# headstage.net
KiCad netlist of a schematic drawn in EAGLE
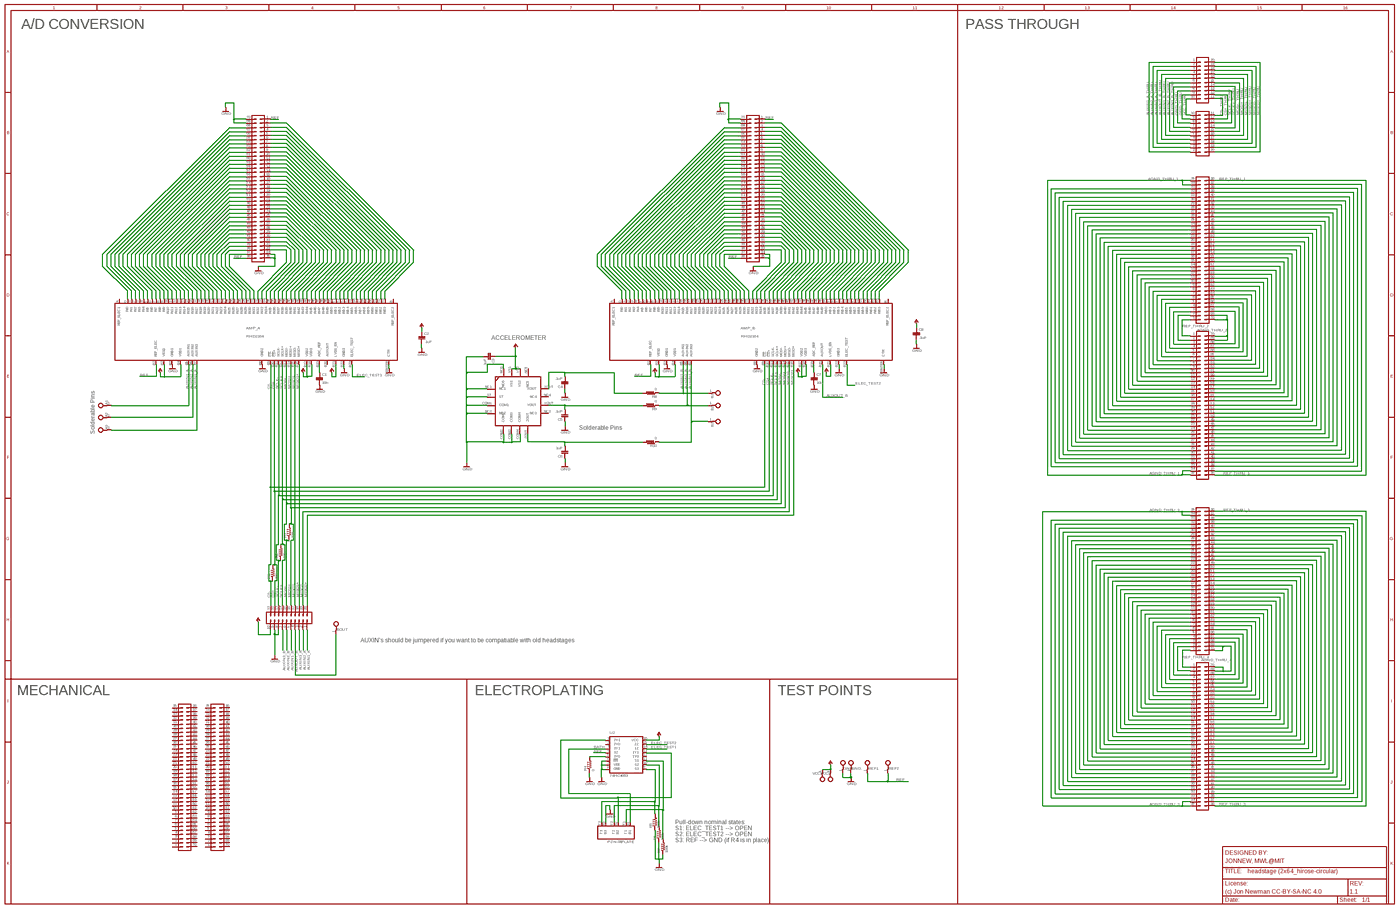
[diagram p0: schematic, sheet 1, overview]
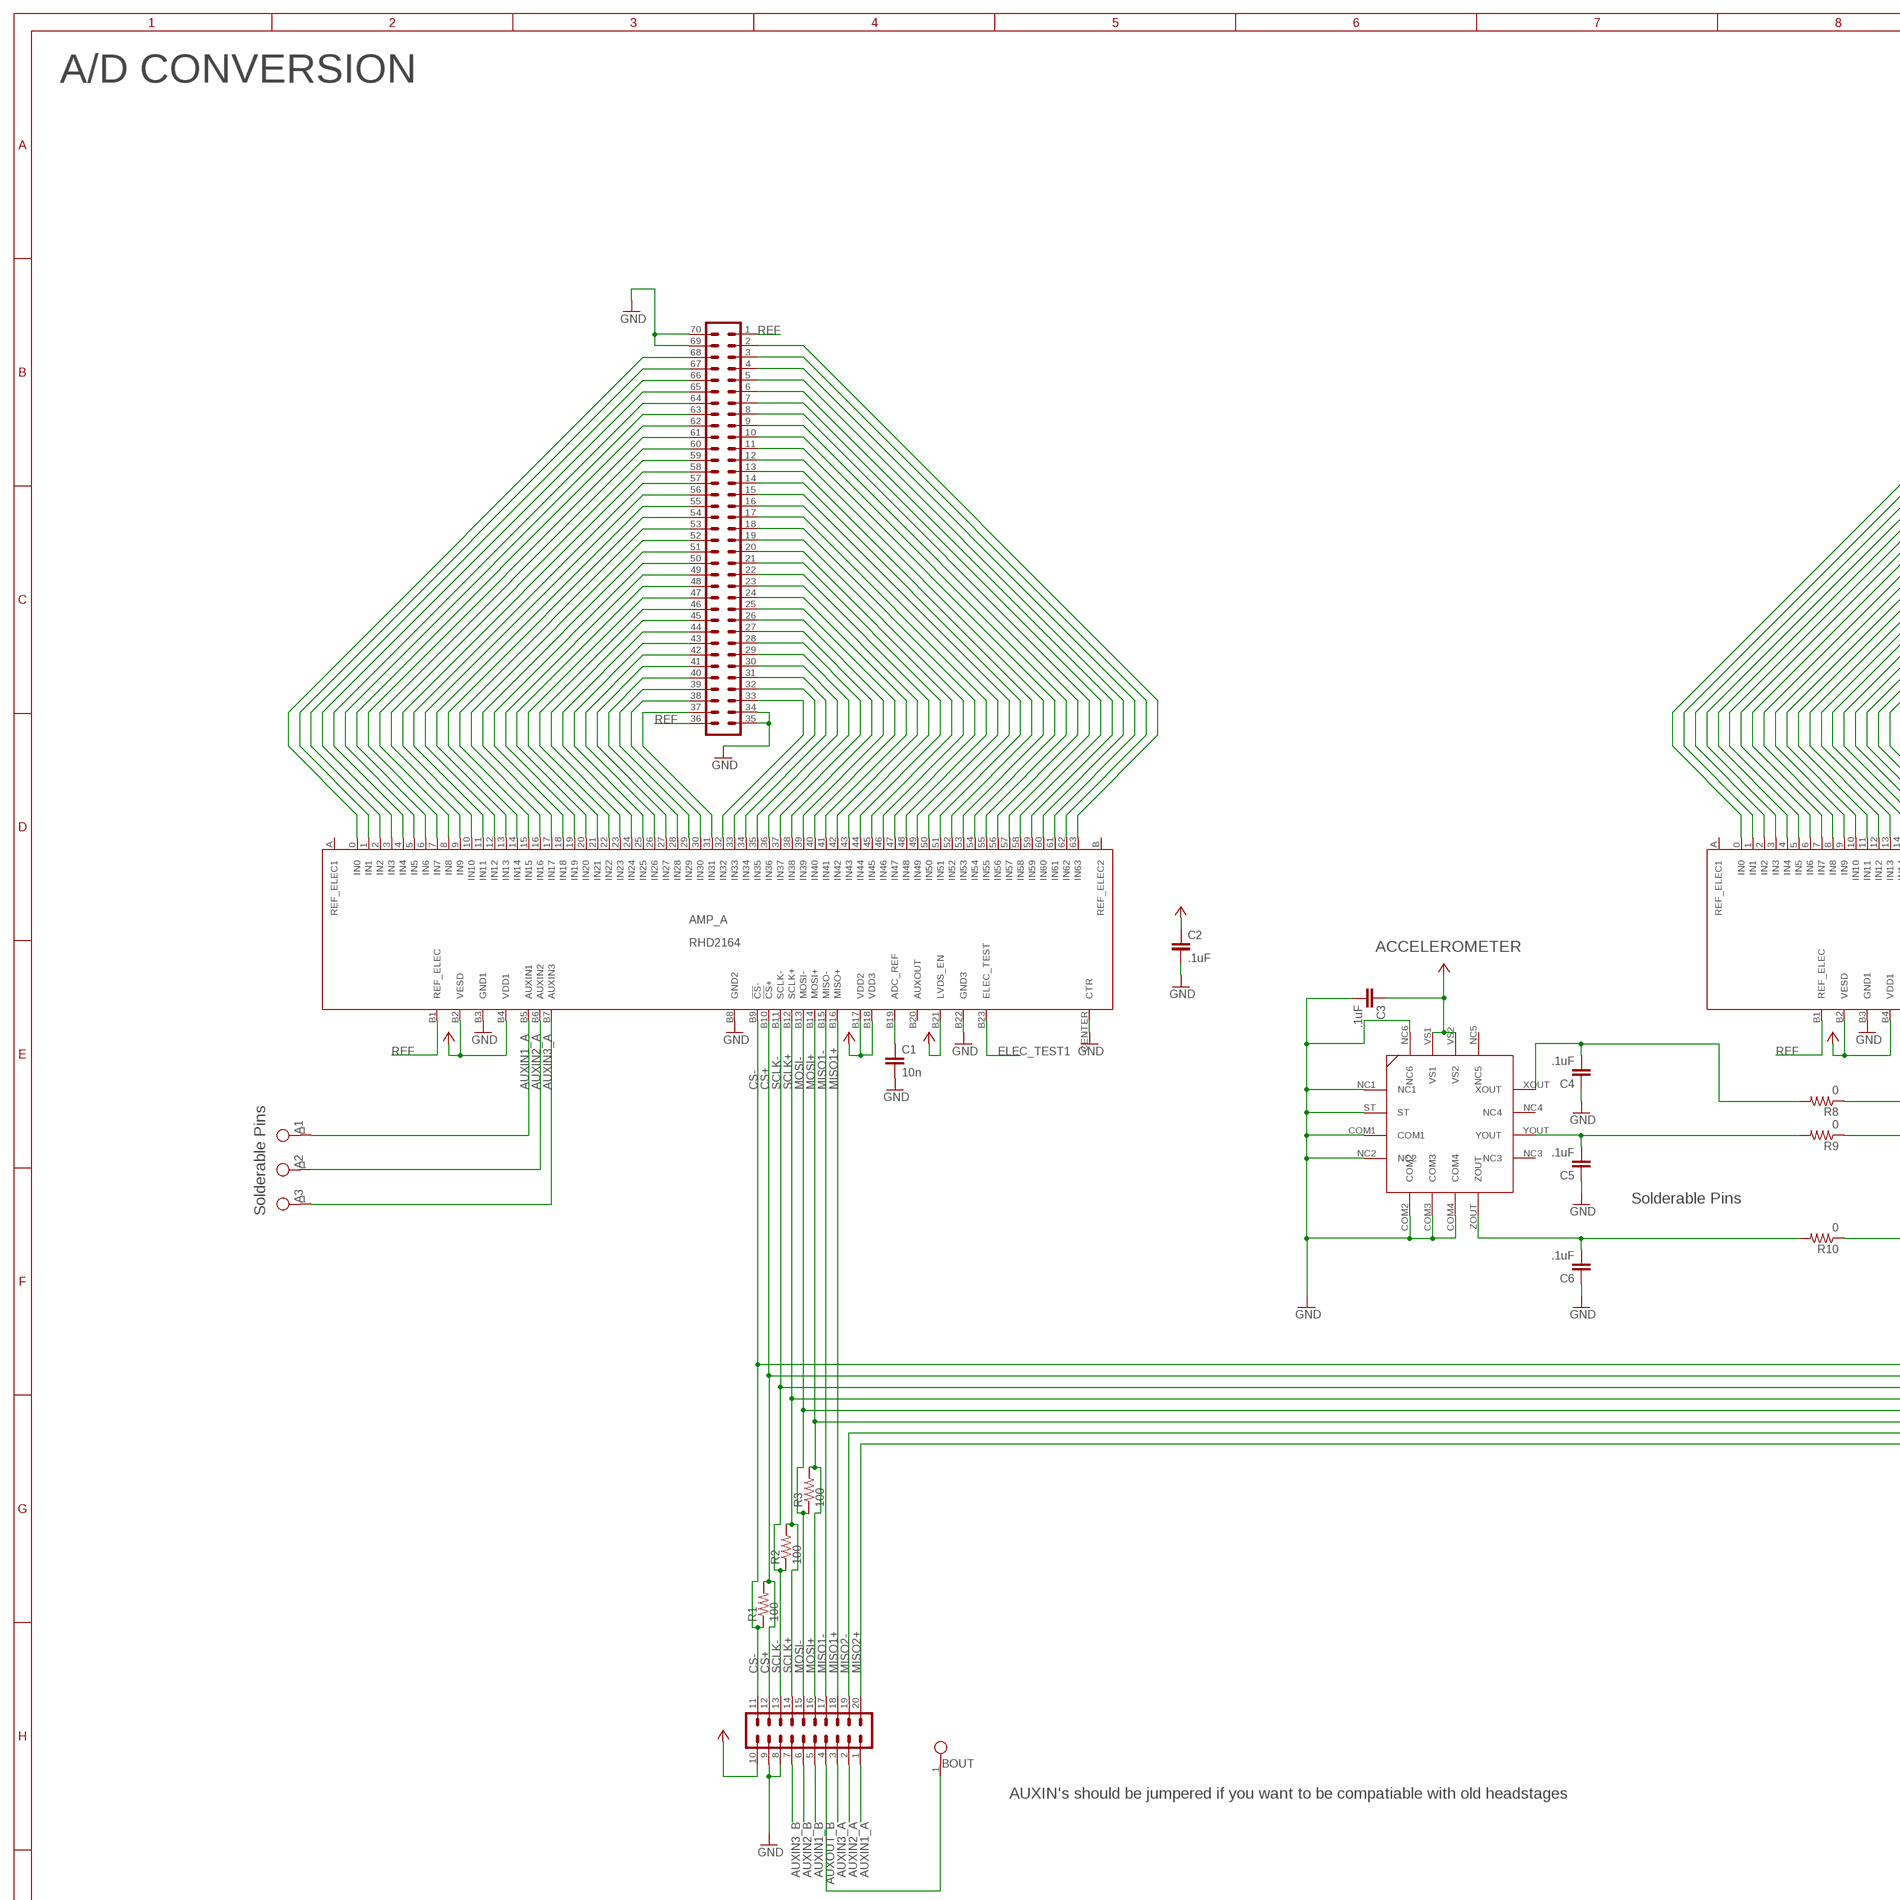
[diagram p1: schematic, sheet 1, part 1 of 4]
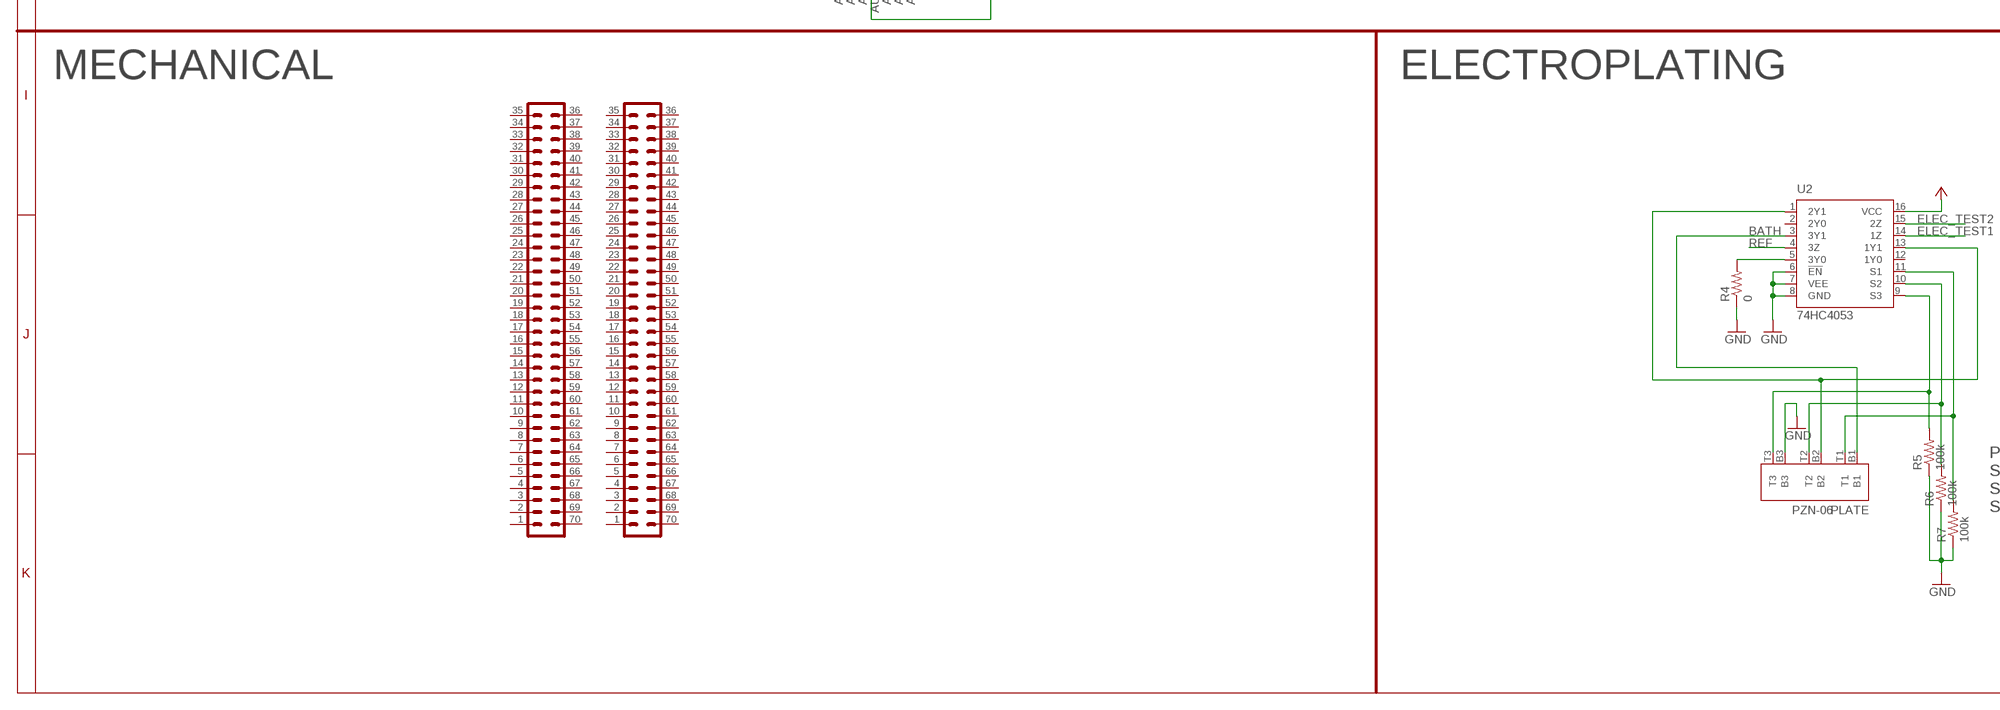
[diagram p2: schematic, sheet 1, part 2 of 4]
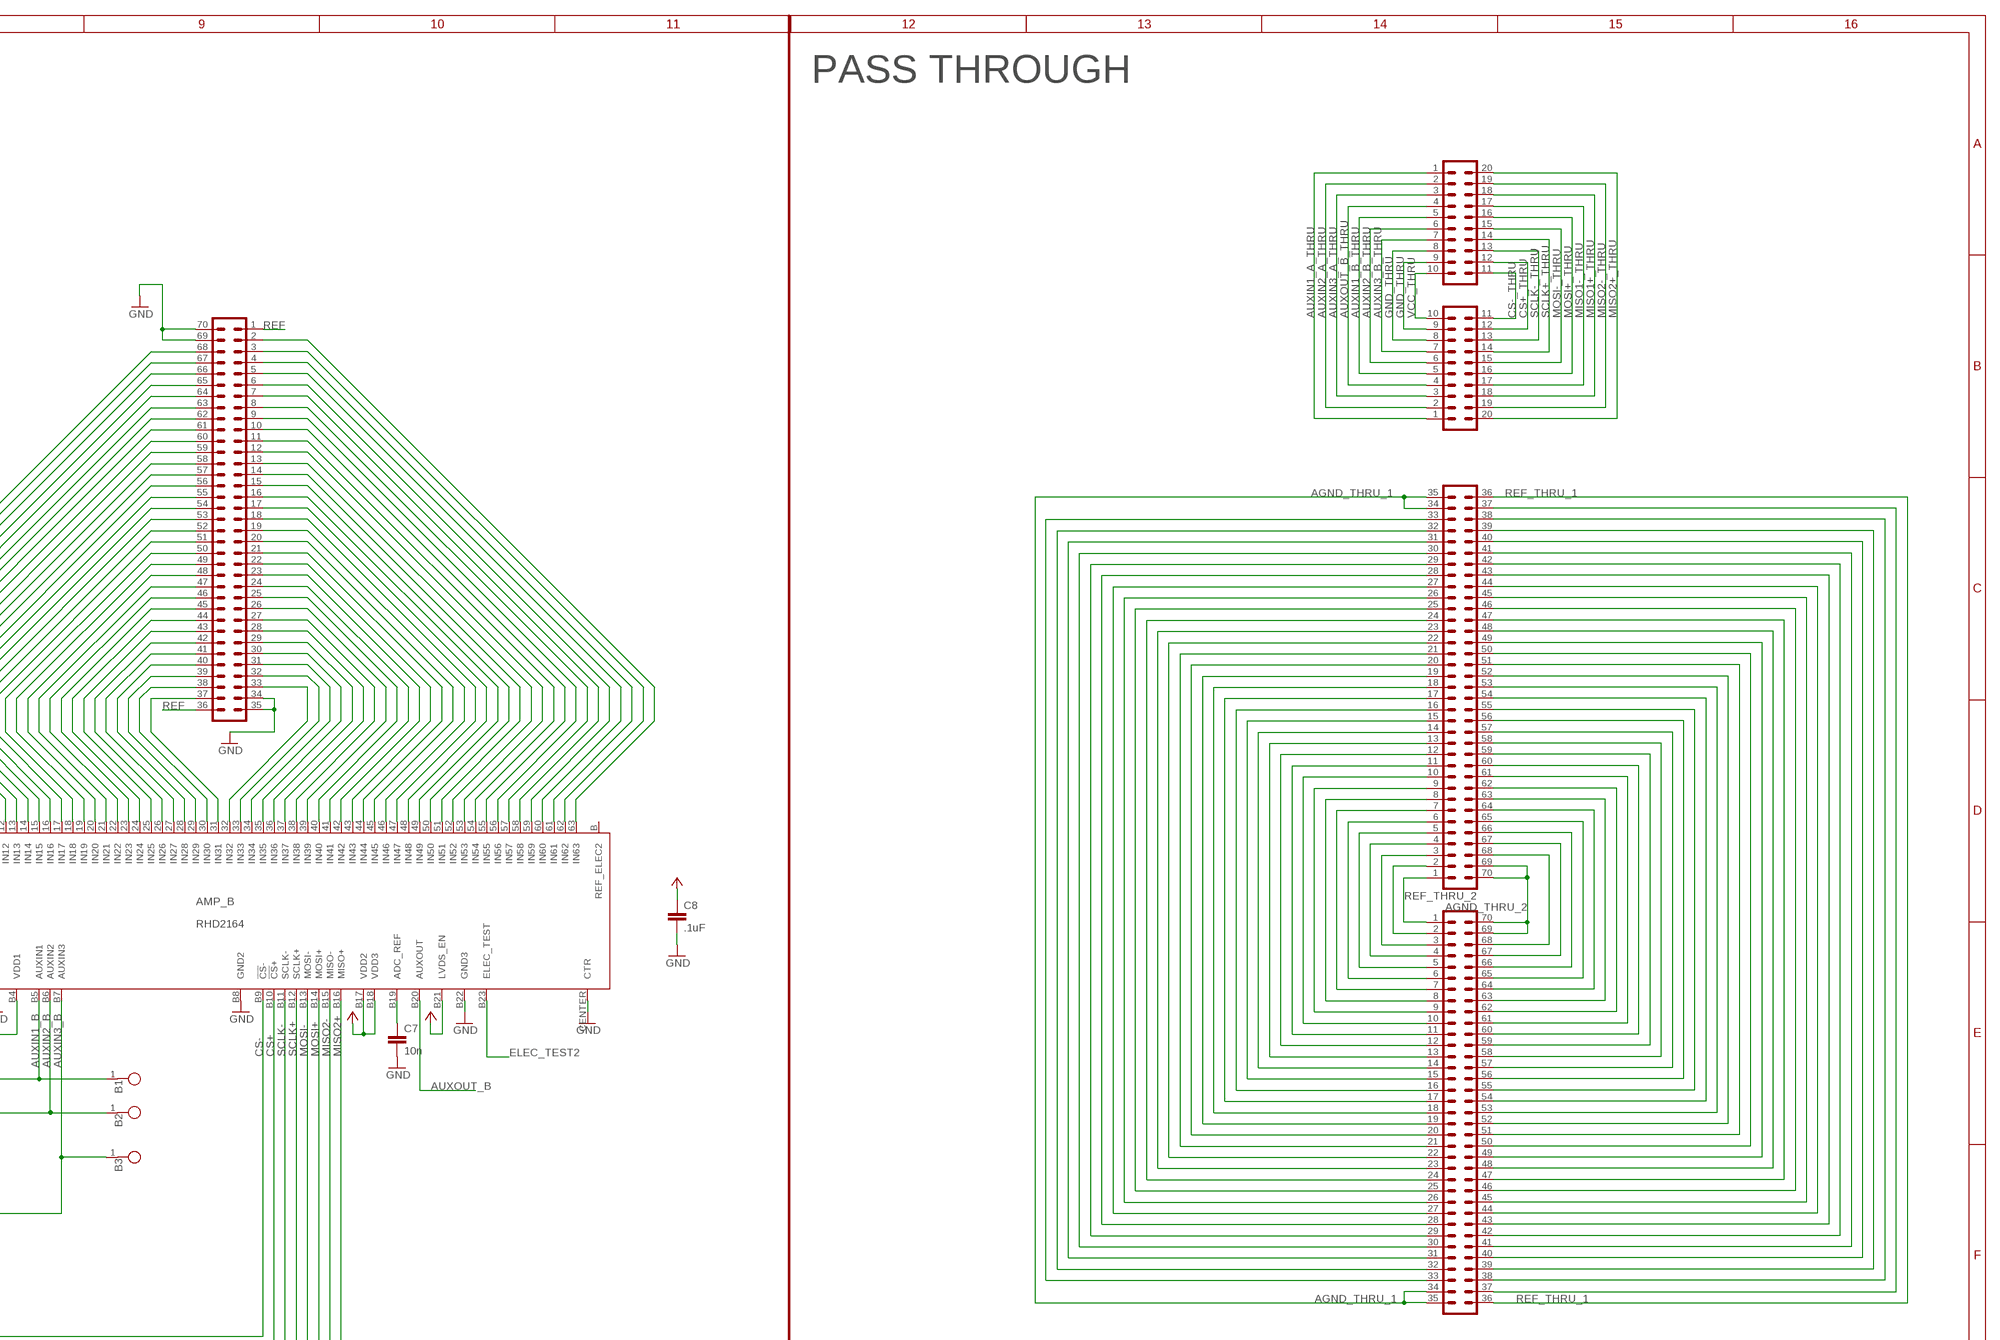
[diagram p3: schematic, sheet 1, part 3 of 4]
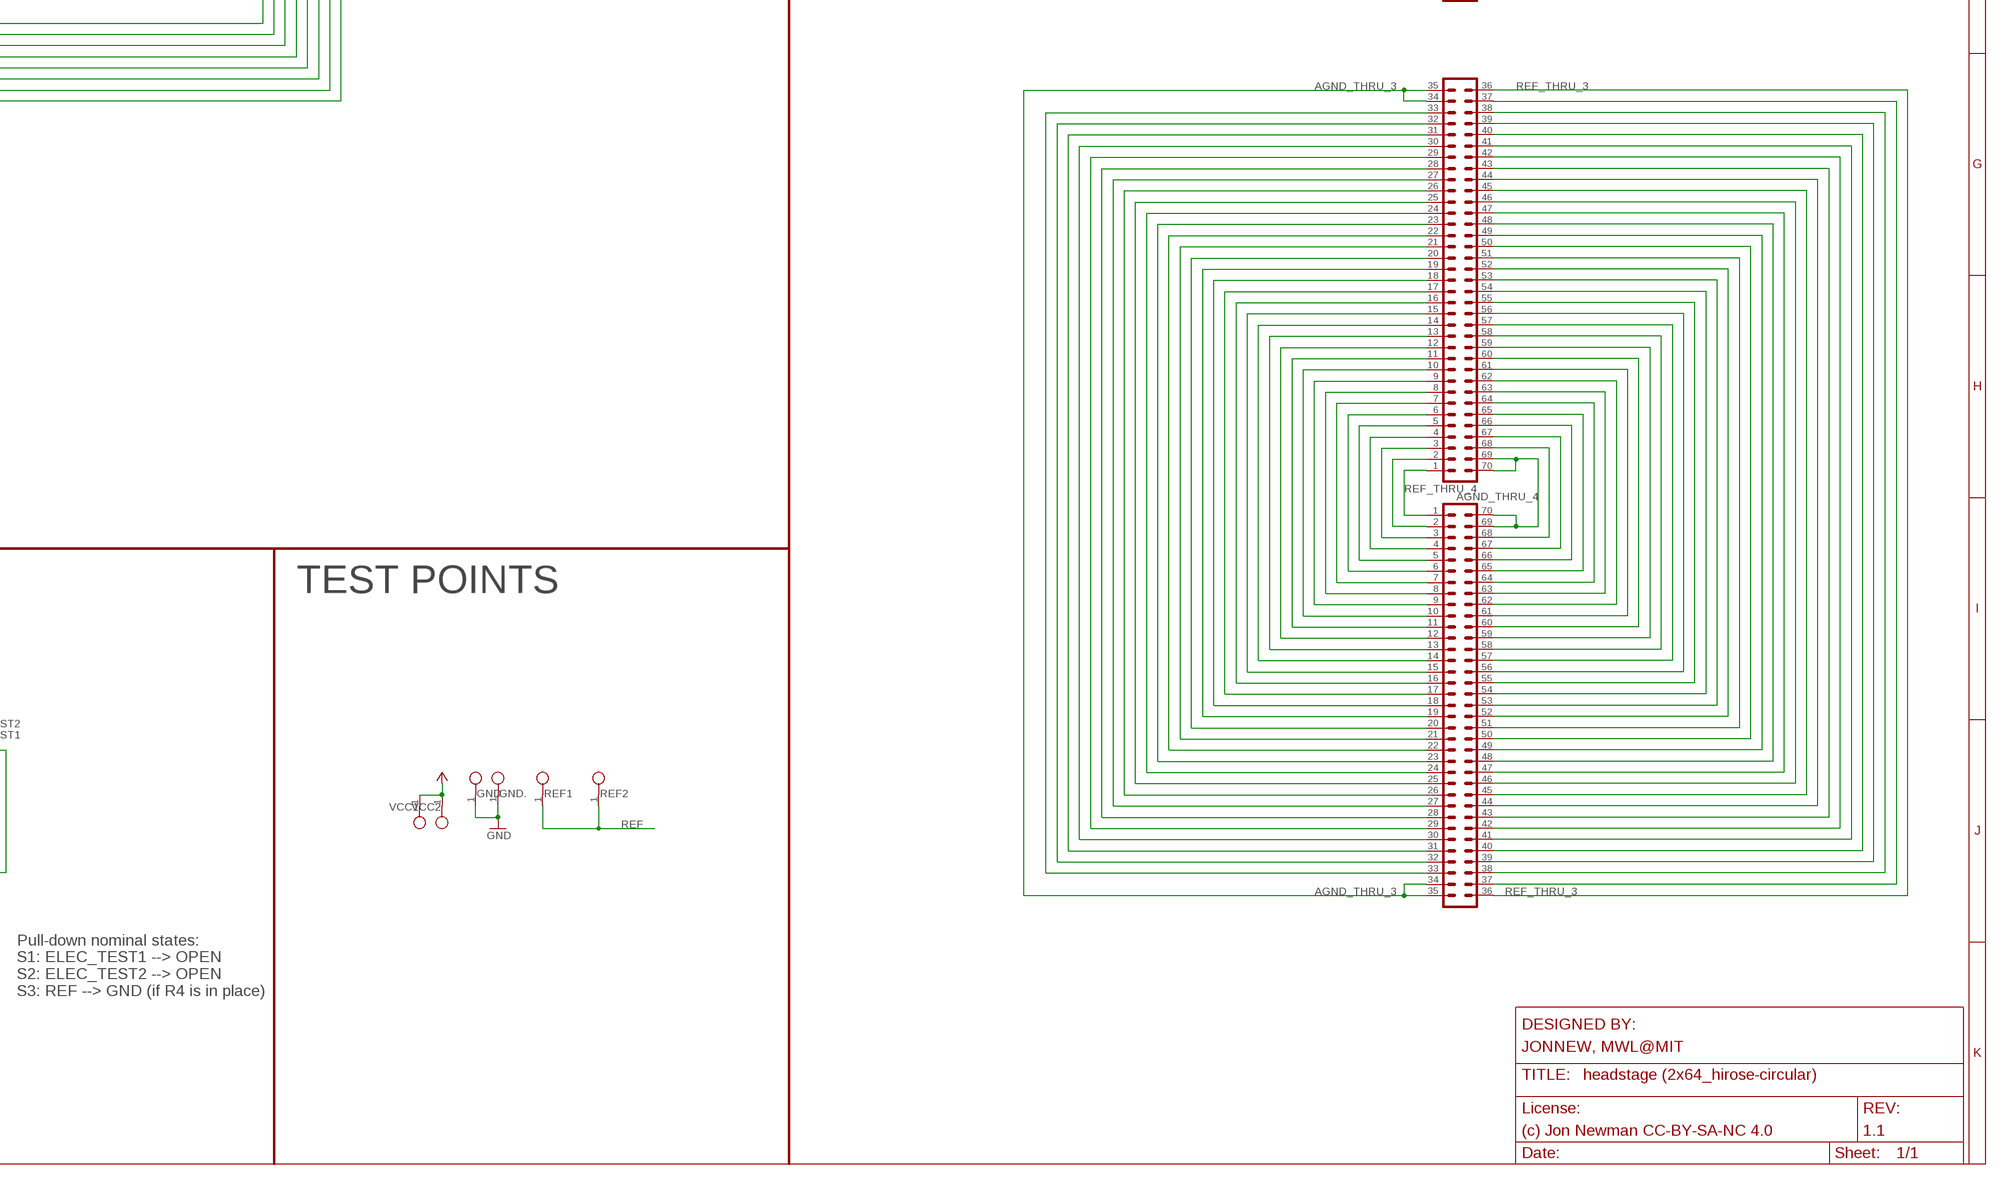
[diagram p4: schematic, sheet 1, part 4 of 4]

(export (version "E")
  (design (tool "Eeschema 10.0.6"))
  (components
    (comp (ref "A1")
      (value "TESTPOINT_SMALL")
      (footprint "eagle-import:TESTPOINT_SMALL")
      (libsource (lib "eagle-import") (part "TESTPOINT_SMALL"))
    )
    (comp (ref "A2")
      (value "TESTPOINT_SMALL")
      (footprint "eagle-import:TESTPOINT_SMALL")
      (libsource (lib "eagle-import") (part "TESTPOINT_SMALL"))
    )
    (comp (ref "A3")
      (value "TESTPOINT_SMALL")
      (footprint "eagle-import:TESTPOINT_SMALL")
      (libsource (lib "eagle-import") (part "TESTPOINT_SMALL"))
    )
    (comp (ref "AIN_BNB")
      (value "DF40REC")
      (footprint "eagle-import:DF40-70REC")
      (libsource (lib "eagle-import") (part "PINHD-2X35_DF40REC"))
    )
    (comp (ref "AIN_BSB")
      (value "DF40REC")
      (footprint "eagle-import:DF40-70REC")
      (libsource (lib "eagle-import") (part "PINHD-2X35_DF40REC"))
    )
    (comp (ref "AMP_A")
      (value "RHD2164")
      (footprint "eagle-import:RHD2164_COB")
      (libsource (lib "eagle-import") (part "RHD2164_COB"))
    )
    (comp (ref "AMP_B")
      (value "RHD2164")
      (footprint "eagle-import:RHD2164_COB")
      (libsource (lib "eagle-import") (part "RHD2164_COB"))
    )
    (comp (ref "ATHRU_BEB")
      (value "DF40REC")
      (footprint "eagle-import:DF40-70REC")
      (libsource (lib "eagle-import") (part "PINHD-2X35_DF40REC"))
    )
    (comp (ref "ATHRU_BWB")
      (value "DF40REC")
      (footprint "eagle-import:DF40-70REC")
      (libsource (lib "eagle-import") (part "PINHD-2X35_DF40REC"))
    )
    (comp (ref "ATHRU_TEB")
      (value "DF40HEAD")
      (footprint "eagle-import:DF40-70HEAD")
      (libsource (lib "eagle-import") (part "PINHD-2X35_DF40HEAD"))
    )
    (comp (ref "ATHRU_TWB")
      (value "DF40HEAD")
      (footprint "eagle-import:DF40-70HEAD")
      (libsource (lib "eagle-import") (part "PINHD-2X35_DF40HEAD"))
    )
    (comp (ref "B1")
      (value "TESTPOINT_SMALL")
      (footprint "eagle-import:TESTPOINT_SMALL")
      (libsource (lib "eagle-import") (part "TESTPOINT_SMALL"))
    )
    (comp (ref "B2")
      (value "TESTPOINT_SMALL")
      (footprint "eagle-import:TESTPOINT_SMALL")
      (libsource (lib "eagle-import") (part "TESTPOINT_SMALL"))
    )
    (comp (ref "B3")
      (value "TESTPOINT_SMALL")
      (footprint "eagle-import:TESTPOINT_SMALL")
      (libsource (lib "eagle-import") (part "TESTPOINT_SMALL"))
    )
    (comp (ref "BOUT")
      (value "TESTPOINT_SMALL")
      (footprint "eagle-import:TESTPOINT_SMALL")
      (libsource (lib "eagle-import") (part "TESTPOINT_SMALL"))
    )
    (comp (ref "C1")
      (value "10n")
      (footprint "eagle-import:0201")
      (libsource (lib "eagle-import") (part "C_0201"))
    )
    (comp (ref "C2")
      (value ".1uF")
      (footprint "eagle-import:0402")
      (libsource (lib "eagle-import") (part "C_0402"))
    )
    (comp (ref "C3")
      (value ".1uF")
      (footprint "eagle-import:0402")
      (libsource (lib "eagle-import") (part "headstage_C_0402"))
    )
    (comp (ref "C4")
      (value ".1uF")
      (footprint "eagle-import:0402")
      (libsource (lib "eagle-import") (part "jonnew_C_0402"))
    )
    (comp (ref "C5")
      (value ".1uF")
      (footprint "eagle-import:0402")
      (libsource (lib "eagle-import") (part "jonnew_C_0402"))
    )
    (comp (ref "C6")
      (value ".1uF")
      (footprint "eagle-import:0402")
      (libsource (lib "eagle-import") (part "jonnew_C_0402"))
    )
    (comp (ref "C7")
      (value "10n")
      (footprint "eagle-import:0201")
      (libsource (lib "eagle-import") (part "C_0201"))
    )
    (comp (ref "C8")
      (value ".1uF")
      (footprint "eagle-import:0402")
      (libsource (lib "eagle-import") (part "C_0402"))
    )
    (comp (ref "DIO_TEA")
      (value "DF40HEAD")
      (footprint "eagle-import:DF40-20HEAD")
      (libsource (lib "eagle-import") (part "PINHD-2X10_DF40-20HEAD"))
    )
    (comp (ref "DTHRU_BNA")
      (value "DF40REC")
      (footprint "eagle-import:DF40-20REC")
      (libsource (lib "eagle-import") (part "PINHD-2X10_DF40-20REC"))
    )
    (comp (ref "DTHRU_TNA")
      (value "DF40HEAD")
      (footprint "eagle-import:DF40-20HEAD")
      (libsource (lib "eagle-import") (part "PINHD-2X10_DF40-20HEAD"))
    )
    (comp (ref "GND")
      (value "GND")
      (footprint "eagle-import:TESTPOINT_SMALL")
      (libsource (lib "eagle-import") (part "TESTPOINT_SMALL"))
    )
    (comp (ref "GND.")
      (value "GND")
      (footprint "eagle-import:TESTPOINT_SMALL")
      (libsource (lib "eagle-import") (part "TESTPOINT_SMALL"))
    )
    (comp (ref "MECH_TNB")
      (value "DF40HEAD")
      (footprint "eagle-import:DF40-70HEAD")
      (libsource (lib "eagle-import") (part "PINHD-2X35_DF40HEAD"))
    )
    (comp (ref "MECH_TSB")
      (value "DF40HEAD")
      (footprint "eagle-import:DF40-70HEAD")
      (libsource (lib "eagle-import") (part "PINHD-2X35_DF40HEAD"))
    )
    (comp (ref "PLATE")
      (value "PZN-06")
      (footprint "eagle-import:OMNETICS_PZN-06-AA")
      (libsource (lib "eagle-import") (part "OMNETICS_PZN-06_SMD"))
    )
    (comp (ref "R1")
      (value "100")
      (footprint "eagle-import:0201")
      (libsource (lib "eagle-import") (part "jonnew_R_0201"))
    )
    (comp (ref "R2")
      (value "100")
      (footprint "eagle-import:0201")
      (libsource (lib "eagle-import") (part "jonnew_R_0201"))
    )
    (comp (ref "R3")
      (value "100")
      (footprint "eagle-import:0201")
      (libsource (lib "eagle-import") (part "jonnew_R_0201"))
    )
    (comp (ref "R4")
      (value "0")
      (footprint "eagle-import:0402")
      (libsource (lib "eagle-import") (part "R_0402"))
    )
    (comp (ref "R5")
      (value "100k")
      (footprint "eagle-import:0201")
      (libsource (lib "eagle-import") (part "R_0201"))
    )
    (comp (ref "R6")
      (value "100k")
      (footprint "eagle-import:0201")
      (libsource (lib "eagle-import") (part "R_0201"))
    )
    (comp (ref "R7")
      (value "100k")
      (footprint "eagle-import:0201")
      (libsource (lib "eagle-import") (part "R_0201"))
    )
    (comp (ref "R8")
      (value "0")
      (footprint "eagle-import:0201")
      (libsource (lib "eagle-import") (part "jonnew_R_0201"))
    )
    (comp (ref "R9")
      (value "0")
      (footprint "eagle-import:0201")
      (libsource (lib "eagle-import") (part "jonnew_R_0201"))
    )
    (comp (ref "R10")
      (value "0")
      (footprint "eagle-import:0201")
      (libsource (lib "eagle-import") (part "jonnew_R_0201"))
    )
    (comp (ref "REF1")
      (value "REF")
      (footprint "eagle-import:TESTPOINT_SMALL")
      (libsource (lib "eagle-import") (part "TESTPOINT_SMALL"))
    )
    (comp (ref "REF2")
      (value "REF")
      (footprint "eagle-import:TESTPOINT_SMALL")
      (libsource (lib "eagle-import") (part "TESTPOINT_SMALL"))
    )
    (comp (ref "U1")
      (value "ADXL335")
      (footprint "eagle-import:ADXL335")
      (libsource (lib "eagle-import") (part "ADXL335"))
    )
    (comp (ref "U2")
      (value "74HC4053")
      (footprint "eagle-import:TSSOP-16")
      (libsource (lib "eagle-import") (part "74HC4053_TSSOP-16"))
    )
    (comp (ref "VCC1")
      (value "VCC")
      (footprint "eagle-import:TESTPOINT_SMALL")
      (libsource (lib "eagle-import") (part "TESTPOINT_SMALL"))
    )
    (comp (ref "VCC2")
      (value "VCC")
      (footprint "eagle-import:TESTPOINT_SMALL")
      (libsource (lib "eagle-import") (part "TESTPOINT_SMALL"))
    )
  )
  (nets
    (net (code "1") (name "/AGND_THRU_1") (class "Default")
      (node (ref "ATHRU_BWB") (pin "34") (pinfunction "34_34") (pintype "bidirectional"))
      (node (ref "ATHRU_BWB") (pin "35") (pinfunction "35_35") (pintype "bidirectional"))
      (node (ref "ATHRU_TWB") (pin "34") (pinfunction "34_34") (pintype "bidirectional"))
      (node (ref "ATHRU_TWB") (pin "35") (pinfunction "35_35") (pintype "bidirectional"))
    )
    (net (code "2") (name "/AGND_THRU_2") (class "Default")
      (node (ref "ATHRU_BWB") (pin "69") (pinfunction "69_69") (pintype "bidirectional"))
      (node (ref "ATHRU_BWB") (pin "70") (pinfunction "70_70") (pintype "bidirectional"))
      (node (ref "ATHRU_TWB") (pin "69") (pinfunction "69_69") (pintype "bidirectional"))
      (node (ref "ATHRU_TWB") (pin "70") (pinfunction "70_70") (pintype "bidirectional"))
    )
    (net (code "3") (name "/AGND_THRU_3") (class "Default")
      (node (ref "ATHRU_BEB") (pin "34") (pinfunction "34_34") (pintype "bidirectional"))
      (node (ref "ATHRU_BEB") (pin "35") (pinfunction "35_35") (pintype "bidirectional"))
      (node (ref "ATHRU_TEB") (pin "34") (pinfunction "34_34") (pintype "bidirectional"))
      (node (ref "ATHRU_TEB") (pin "35") (pinfunction "35_35") (pintype "bidirectional"))
    )
    (net (code "4") (name "/AGND_THRU_4") (class "Default")
      (node (ref "ATHRU_BEB") (pin "69") (pinfunction "69_69") (pintype "bidirectional"))
      (node (ref "ATHRU_BEB") (pin "70") (pinfunction "70_70") (pintype "bidirectional"))
      (node (ref "ATHRU_TEB") (pin "69") (pinfunction "69_69") (pintype "bidirectional"))
      (node (ref "ATHRU_TEB") (pin "70") (pinfunction "70_70") (pintype "bidirectional"))
    )
    (net (code "5") (name "/AUXIN1_A") (class "Default")
      (node (ref "A1") (pin "1") (pinfunction "1_1") (pintype "passive"))
      (node (ref "AMP_A") (pin "B5") (pinfunction "AUXIN1_B5") (pintype "input"))
      (node (ref "DIO_TEA") (pin "1") (pinfunction "1_1") (pintype "bidirectional"))
    )
    (net (code "6") (name "/AUXIN1_A_THRU") (class "Default")
      (node (ref "DTHRU_BNA") (pin "1") (pinfunction "1_1") (pintype "bidirectional"))
      (node (ref "DTHRU_TNA") (pin "1") (pinfunction "1_1") (pintype "bidirectional"))
    )
    (net (code "7") (name "/AUXIN1_B") (class "Default")
      (node (ref "AMP_B") (pin "B5") (pinfunction "AUXIN1_B5") (pintype "input"))
      (node (ref "B1") (pin "1") (pinfunction "1_1") (pintype "passive"))
      (node (ref "DIO_TEA") (pin "5") (pinfunction "5_5") (pintype "bidirectional"))
      (node (ref "R8") (pin "1") (pinfunction "1_1") (pintype "passive"))
    )
    (net (code "8") (name "/AUXIN1_B_THRU") (class "Default")
      (node (ref "DTHRU_BNA") (pin "5") (pinfunction "5_5") (pintype "bidirectional"))
      (node (ref "DTHRU_TNA") (pin "5") (pinfunction "5_5") (pintype "bidirectional"))
    )
    (net (code "9") (name "/AUXIN2_A") (class "Default")
      (node (ref "A2") (pin "1") (pinfunction "1_1") (pintype "passive"))
      (node (ref "AMP_A") (pin "B6") (pinfunction "AUXIN2_B6") (pintype "input"))
      (node (ref "DIO_TEA") (pin "2") (pinfunction "2_2") (pintype "bidirectional"))
    )
    (net (code "10") (name "/AUXIN2_A_THRU") (class "Default")
      (node (ref "DTHRU_BNA") (pin "2") (pinfunction "2_2") (pintype "bidirectional"))
      (node (ref "DTHRU_TNA") (pin "2") (pinfunction "2_2") (pintype "bidirectional"))
    )
    (net (code "11") (name "/AUXIN2_B") (class "Default")
      (node (ref "AMP_B") (pin "B6") (pinfunction "AUXIN2_B6") (pintype "input"))
      (node (ref "B2") (pin "1") (pinfunction "1_1") (pintype "passive"))
      (node (ref "DIO_TEA") (pin "6") (pinfunction "6_6") (pintype "bidirectional"))
      (node (ref "R9") (pin "1") (pinfunction "1_1") (pintype "passive"))
    )
    (net (code "12") (name "/AUXIN2_B_THRU") (class "Default")
      (node (ref "DTHRU_BNA") (pin "6") (pinfunction "6_6") (pintype "bidirectional"))
      (node (ref "DTHRU_TNA") (pin "6") (pinfunction "6_6") (pintype "bidirectional"))
    )
    (net (code "13") (name "/AUXIN3_A") (class "Default")
      (node (ref "A3") (pin "1") (pinfunction "1_1") (pintype "passive"))
      (node (ref "AMP_A") (pin "B7") (pinfunction "AUXIN3_B7") (pintype "input"))
      (node (ref "DIO_TEA") (pin "3") (pinfunction "3_3") (pintype "bidirectional"))
    )
    (net (code "14") (name "/AUXIN3_A_THRU") (class "Default")
      (node (ref "DTHRU_BNA") (pin "3") (pinfunction "3_3") (pintype "bidirectional"))
      (node (ref "DTHRU_TNA") (pin "3") (pinfunction "3_3") (pintype "bidirectional"))
    )
    (net (code "15") (name "/AUXIN3_B") (class "Default")
      (node (ref "AMP_B") (pin "B7") (pinfunction "AUXIN3_B7") (pintype "input"))
      (node (ref "B3") (pin "1") (pinfunction "1_1") (pintype "passive"))
      (node (ref "DIO_TEA") (pin "7") (pinfunction "7_7") (pintype "bidirectional"))
      (node (ref "R10") (pin "1") (pinfunction "1_1") (pintype "passive"))
    )
    (net (code "16") (name "/AUXIN3_B_THRU") (class "Default")
      (node (ref "DTHRU_BNA") (pin "7") (pinfunction "7_7") (pintype "bidirectional"))
      (node (ref "DTHRU_TNA") (pin "7") (pinfunction "7_7") (pintype "bidirectional"))
    )
    (net (code "17") (name "/AUXOUT_B") (class "Default")
      (node (ref "AMP_B") (pin "B20") (pinfunction "AUXOUT_B20") (pintype "tri_state"))
      (node (ref "BOUT") (pin "1") (pinfunction "1_1") (pintype "passive"))
      (node (ref "DIO_TEA") (pin "4") (pinfunction "4_4") (pintype "bidirectional"))
    )
    (net (code "18") (name "/AUXOUT_B_THRU") (class "Default")
      (node (ref "DTHRU_BNA") (pin "4") (pinfunction "4_4") (pintype "bidirectional"))
      (node (ref "DTHRU_TNA") (pin "4") (pinfunction "4_4") (pintype "bidirectional"))
    )
    (net (code "19") (name "/BATH") (class "Default")
      (node (ref "PLATE") (pin "B1") (pinfunction "B1_B1") (pintype "bidirectional"))
      (node (ref "U2") (pin "3") (pinfunction "3Y1_3") (pintype "bidirectional"))
    )
    (net (code "20") (name "/CS+") (class "Default")
      (node (ref "AMP_A") (pin "B10") (pinfunction "~{CS}+_B10") (pintype "input"))
      (node (ref "AMP_B") (pin "B10") (pinfunction "~{CS}+_B10") (pintype "input"))
      (node (ref "DIO_TEA") (pin "12") (pinfunction "12_12") (pintype "bidirectional"))
      (node (ref "R1") (pin "2") (pinfunction "2_2") (pintype "passive"))
    )
    (net (code "21") (name "/CS+_THRU") (class "Default")
      (node (ref "DTHRU_BNA") (pin "12") (pinfunction "12_12") (pintype "bidirectional"))
      (node (ref "DTHRU_TNA") (pin "12") (pinfunction "12_12") (pintype "bidirectional"))
    )
    (net (code "22") (name "/CS-") (class "Default")
      (node (ref "AMP_A") (pin "B9") (pinfunction "~{CS}-_B9") (pintype "input"))
      (node (ref "AMP_B") (pin "B9") (pinfunction "~{CS}-_B9") (pintype "input"))
      (node (ref "DIO_TEA") (pin "11") (pinfunction "11_11") (pintype "bidirectional"))
      (node (ref "R1") (pin "1") (pinfunction "1_1") (pintype "passive"))
    )
    (net (code "23") (name "/CS-_THRU") (class "Default")
      (node (ref "DTHRU_BNA") (pin "11") (pinfunction "11_11") (pintype "bidirectional"))
      (node (ref "DTHRU_TNA") (pin "11") (pinfunction "11_11") (pintype "bidirectional"))
    )
    (net (code "24") (name "/ELEC_TEST1") (class "Default")
      (node (ref "AMP_A") (pin "B23") (pinfunction "ELEC_TEST_B23") (pintype "input"))
      (node (ref "U2") (pin "14") (pinfunction "1Z_14") (pintype "bidirectional"))
    )
    (net (code "25") (name "/ELEC_TEST2") (class "Default")
      (node (ref "AMP_B") (pin "B23") (pinfunction "ELEC_TEST_B23") (pintype "input"))
      (node (ref "U2") (pin "15") (pinfunction "2Z_15") (pintype "bidirectional"))
    )
    (net (code "26") (name "/GND_THRU") (class "Default")
      (node (ref "DTHRU_BNA") (pin "8") (pinfunction "8_8") (pintype "bidirectional"))
      (node (ref "DTHRU_BNA") (pin "9") (pinfunction "9_9") (pintype "bidirectional"))
      (node (ref "DTHRU_TNA") (pin "8") (pinfunction "8_8") (pintype "bidirectional"))
      (node (ref "DTHRU_TNA") (pin "9") (pinfunction "9_9") (pintype "bidirectional"))
    )
    (net (code "27") (name "/MISO1+") (class "Default")
      (node (ref "AMP_A") (pin "B16") (pinfunction "MISO+_B16") (pintype "output"))
      (node (ref "DIO_TEA") (pin "18") (pinfunction "18_18") (pintype "bidirectional"))
    )
    (net (code "28") (name "/MISO1+_THRU") (class "Default")
      (node (ref "DTHRU_BNA") (pin "18") (pinfunction "18_18") (pintype "bidirectional"))
      (node (ref "DTHRU_TNA") (pin "18") (pinfunction "18_18") (pintype "bidirectional"))
    )
    (net (code "29") (name "/MISO1-") (class "Default")
      (node (ref "AMP_A") (pin "B15") (pinfunction "MISO-_B15") (pintype "output"))
      (node (ref "DIO_TEA") (pin "17") (pinfunction "17_17") (pintype "bidirectional"))
    )
    (net (code "30") (name "/MISO1-_THRU") (class "Default")
      (node (ref "DTHRU_BNA") (pin "17") (pinfunction "17_17") (pintype "bidirectional"))
      (node (ref "DTHRU_TNA") (pin "17") (pinfunction "17_17") (pintype "bidirectional"))
    )
    (net (code "31") (name "/MISO2+") (class "Default")
      (node (ref "AMP_B") (pin "B16") (pinfunction "MISO+_B16") (pintype "output"))
      (node (ref "DIO_TEA") (pin "20") (pinfunction "20_20") (pintype "bidirectional"))
    )
    (net (code "32") (name "/MISO2+_THRU") (class "Default")
      (node (ref "DTHRU_BNA") (pin "20") (pinfunction "20_20") (pintype "bidirectional"))
      (node (ref "DTHRU_TNA") (pin "20") (pinfunction "20_20") (pintype "bidirectional"))
    )
    (net (code "33") (name "/MISO2-") (class "Default")
      (node (ref "AMP_B") (pin "B15") (pinfunction "MISO-_B15") (pintype "output"))
      (node (ref "DIO_TEA") (pin "19") (pinfunction "19_19") (pintype "bidirectional"))
    )
    (net (code "34") (name "/MISO2-_THRU") (class "Default")
      (node (ref "DTHRU_BNA") (pin "19") (pinfunction "19_19") (pintype "bidirectional"))
      (node (ref "DTHRU_TNA") (pin "19") (pinfunction "19_19") (pintype "bidirectional"))
    )
    (net (code "35") (name "/MOSI+") (class "Default")
      (node (ref "AMP_A") (pin "B14") (pinfunction "MOSI+_B14") (pintype "input"))
      (node (ref "AMP_B") (pin "B14") (pinfunction "MOSI+_B14") (pintype "input"))
      (node (ref "DIO_TEA") (pin "16") (pinfunction "16_16") (pintype "bidirectional"))
      (node (ref "R3") (pin "2") (pinfunction "2_2") (pintype "passive"))
    )
    (net (code "36") (name "/MOSI+_THRU") (class "Default")
      (node (ref "DTHRU_BNA") (pin "16") (pinfunction "16_16") (pintype "bidirectional"))
      (node (ref "DTHRU_TNA") (pin "16") (pinfunction "16_16") (pintype "bidirectional"))
    )
    (net (code "37") (name "/MOSI-") (class "Default")
      (node (ref "AMP_A") (pin "B13") (pinfunction "MOSI-_B13") (pintype "input"))
      (node (ref "AMP_B") (pin "B13") (pinfunction "MOSI-_B13") (pintype "input"))
      (node (ref "DIO_TEA") (pin "15") (pinfunction "15_15") (pintype "bidirectional"))
      (node (ref "R3") (pin "1") (pinfunction "1_1") (pintype "passive"))
    )
    (net (code "38") (name "/MOSI-_THRU") (class "Default")
      (node (ref "DTHRU_BNA") (pin "15") (pinfunction "15_15") (pintype "bidirectional"))
      (node (ref "DTHRU_TNA") (pin "15") (pinfunction "15_15") (pintype "bidirectional"))
    )
    (net (code "39") (name "/REF") (class "Default")
      (node (ref "AIN_BNB") (pin "1") (pinfunction "1_1") (pintype "bidirectional"))
      (node (ref "AIN_BNB") (pin "36") (pinfunction "36_36") (pintype "bidirectional"))
      (node (ref "AIN_BSB") (pin "1") (pinfunction "1_1") (pintype "bidirectional"))
      (node (ref "AIN_BSB") (pin "36") (pinfunction "36_36") (pintype "bidirectional"))
      (node (ref "AMP_A") (pin "B1") (pinfunction "REF_ELEC_B1") (pintype "input"))
      (node (ref "AMP_B") (pin "B1") (pinfunction "REF_ELEC_B1") (pintype "input"))
      (node (ref "REF1") (pin "1") (pinfunction "1_1") (pintype "passive"))
      (node (ref "REF2") (pin "1") (pinfunction "1_1") (pintype "passive"))
      (node (ref "U2") (pin "4") (pinfunction "3Z_4") (pintype "bidirectional"))
    )
    (net (code "40") (name "/REF_THRU_1") (class "Default")
      (node (ref "ATHRU_BWB") (pin "36") (pinfunction "36_36") (pintype "bidirectional"))
      (node (ref "ATHRU_TWB") (pin "36") (pinfunction "36_36") (pintype "bidirectional"))
    )
    (net (code "41") (name "/REF_THRU_2") (class "Default")
      (node (ref "ATHRU_BWB") (pin "1") (pinfunction "1_1") (pintype "bidirectional"))
      (node (ref "ATHRU_TWB") (pin "1") (pinfunction "1_1") (pintype "bidirectional"))
    )
    (net (code "42") (name "/REF_THRU_3") (class "Default")
      (node (ref "ATHRU_BEB") (pin "36") (pinfunction "36_36") (pintype "bidirectional"))
      (node (ref "ATHRU_TEB") (pin "36") (pinfunction "36_36") (pintype "bidirectional"))
    )
    (net (code "43") (name "/REF_THRU_4") (class "Default")
      (node (ref "ATHRU_BEB") (pin "1") (pinfunction "1_1") (pintype "bidirectional"))
      (node (ref "ATHRU_TEB") (pin "1") (pinfunction "1_1") (pintype "bidirectional"))
    )
    (net (code "44") (name "/SCLK+") (class "Default")
      (node (ref "AMP_A") (pin "B12") (pinfunction "SCLK+_B12") (pintype "input"))
      (node (ref "AMP_B") (pin "B12") (pinfunction "SCLK+_B12") (pintype "input"))
      (node (ref "DIO_TEA") (pin "14") (pinfunction "14_14") (pintype "bidirectional"))
      (node (ref "R2") (pin "2") (pinfunction "2_2") (pintype "passive"))
    )
    (net (code "45") (name "/SCLK+_THRU") (class "Default")
      (node (ref "DTHRU_BNA") (pin "14") (pinfunction "14_14") (pintype "bidirectional"))
      (node (ref "DTHRU_TNA") (pin "14") (pinfunction "14_14") (pintype "bidirectional"))
    )
    (net (code "46") (name "/SCLK-") (class "Default")
      (node (ref "AMP_A") (pin "B11") (pinfunction "SCLK-_B11") (pintype "input"))
      (node (ref "AMP_B") (pin "B11") (pinfunction "SCLK-_B11") (pintype "input"))
      (node (ref "DIO_TEA") (pin "13") (pinfunction "13_13") (pintype "bidirectional"))
      (node (ref "R2") (pin "1") (pinfunction "1_1") (pintype "passive"))
    )
    (net (code "47") (name "/SCLK-_THRU") (class "Default")
      (node (ref "DTHRU_BNA") (pin "13") (pinfunction "13_13") (pintype "bidirectional"))
      (node (ref "DTHRU_TNA") (pin "13") (pinfunction "13_13") (pintype "bidirectional"))
    )
    (net (code "48") (name "/VCC_THRU") (class "Default")
      (node (ref "DTHRU_BNA") (pin "10") (pinfunction "10_10") (pintype "bidirectional"))
      (node (ref "DTHRU_TNA") (pin "10") (pinfunction "10_10") (pintype "bidirectional"))
    )
    (net (code "49") (name "GND") (class "Default")
      (node (ref "AIN_BNB") (pin "34") (pinfunction "34_34") (pintype "bidirectional"))
      (node (ref "AIN_BNB") (pin "35") (pinfunction "35_35") (pintype "bidirectional"))
      (node (ref "AIN_BNB") (pin "69") (pinfunction "69_69") (pintype "bidirectional"))
      (node (ref "AIN_BNB") (pin "70") (pinfunction "70_70") (pintype "bidirectional"))
      (node (ref "AIN_BSB") (pin "34") (pinfunction "34_34") (pintype "bidirectional"))
      (node (ref "AIN_BSB") (pin "35") (pinfunction "35_35") (pintype "bidirectional"))
      (node (ref "AIN_BSB") (pin "69") (pinfunction "69_69") (pintype "bidirectional"))
      (node (ref "AIN_BSB") (pin "70") (pinfunction "70_70") (pintype "bidirectional"))
      (node (ref "AMP_A") (pin "B22") (pinfunction "GND3_B22") (pintype "power_in"))
      (node (ref "AMP_A") (pin "B3") (pinfunction "GND1_B3") (pintype "power_in"))
      (node (ref "AMP_A") (pin "B8") (pinfunction "GND2_B8") (pintype "power_in"))
      (node (ref "AMP_A") (pin "CENTER") (pinfunction "CTR_CENTER") (pintype "power_in"))
      (node (ref "AMP_B") (pin "B22") (pinfunction "GND3_B22") (pintype "power_in"))
      (node (ref "AMP_B") (pin "B3") (pinfunction "GND1_B3") (pintype "power_in"))
      (node (ref "AMP_B") (pin "B8") (pinfunction "GND2_B8") (pintype "power_in"))
      (node (ref "AMP_B") (pin "CENTER") (pinfunction "CTR_CENTER") (pintype "power_in"))
      (node (ref "C1") (pin "2") (pinfunction "2_2") (pintype "passive"))
      (node (ref "C2") (pin "2") (pinfunction "2_2") (pintype "passive"))
      (node (ref "C3") (pin "2") (pinfunction "2_2") (pintype "passive"))
      (node (ref "C4") (pin "1") (pinfunction "1_1") (pintype "passive"))
      (node (ref "C5") (pin "1") (pinfunction "1_1") (pintype "passive"))
      (node (ref "C6") (pin "1") (pinfunction "1_1") (pintype "passive"))
      (node (ref "C7") (pin "2") (pinfunction "2_2") (pintype "passive"))
      (node (ref "C8") (pin "2") (pinfunction "2_2") (pintype "passive"))
      (node (ref "DIO_TEA") (pin "8") (pinfunction "8_8") (pintype "bidirectional"))
      (node (ref "DIO_TEA") (pin "9") (pinfunction "9_9") (pintype "bidirectional"))
      (node (ref "GND") (pin "1") (pinfunction "1_1") (pintype "passive"))
      (node (ref "GND.") (pin "1") (pinfunction "1_1") (pintype "passive"))
      (node (ref "PLATE") (pin "B3") (pinfunction "B3_B3") (pintype "bidirectional"))
      (node (ref "R4") (pin "1") (pinfunction "1_1") (pintype "passive"))
      (node (ref "R5") (pin "1") (pinfunction "1_1") (pintype "passive"))
      (node (ref "R6") (pin "1") (pinfunction "1_1") (pintype "passive"))
      (node (ref "R7") (pin "1") (pinfunction "1_1") (pintype "passive"))
      (node (ref "U1") (pin "COM1") (pinfunction "COM1_COM1") (pintype "bidirectional"))
      (node (ref "U1") (pin "COM2") (pinfunction "COM2_COM2") (pintype "bidirectional"))
      (node (ref "U1") (pin "COM3") (pinfunction "COM3_COM3") (pintype "bidirectional"))
      (node (ref "U1") (pin "COM4") (pinfunction "COM4_COM4") (pintype "bidirectional"))
      (node (ref "U1") (pin "NC1") (pinfunction "NC1_NC1") (pintype "bidirectional"))
      (node (ref "U1") (pin "NC2") (pinfunction "NC2_NC2") (pintype "bidirectional"))
      (node (ref "U1") (pin "NC6") (pinfunction "NC6_NC6") (pintype "bidirectional"))
      (node (ref "U1") (pin "ST") (pinfunction "ST_ST") (pintype "bidirectional"))
      (node (ref "U2") (pin "6") (pinfunction "~{EN}_6") (pintype "input"))
      (node (ref "U2") (pin "7") (pinfunction "VEE_7") (pintype "power_in"))
      (node (ref "U2") (pin "8") (pinfunction "GND_8") (pintype "power_in"))
    )
    (net (code "50") (name "Net-(AMP_A-ADC_REF)") (class "Default")
      (node (ref "AMP_A") (pin "B19") (pinfunction "ADC_REF_B19") (pintype "passive"))
      (node (ref "C1") (pin "1") (pinfunction "1_1") (pintype "passive"))
    )
    (net (code "51") (name "Net-(AMP_A-IN0)") (class "Default")
      (node (ref "AIN_BNB") (pin "68") (pinfunction "68_68") (pintype "bidirectional"))
      (node (ref "AMP_A") (pin "0") (pinfunction "IN0_0") (pintype "input"))
    )
    (net (code "52") (name "Net-(AMP_A-IN1)") (class "Default")
      (node (ref "AIN_BNB") (pin "67") (pinfunction "67_67") (pintype "bidirectional"))
      (node (ref "AMP_A") (pin "1") (pinfunction "IN1_1") (pintype "input"))
    )
    (net (code "53") (name "Net-(AMP_A-IN2)") (class "Default")
      (node (ref "AIN_BNB") (pin "66") (pinfunction "66_66") (pintype "bidirectional"))
      (node (ref "AMP_A") (pin "2") (pinfunction "IN2_2") (pintype "input"))
    )
    (net (code "54") (name "Net-(AMP_A-IN3)") (class "Default")
      (node (ref "AIN_BNB") (pin "65") (pinfunction "65_65") (pintype "bidirectional"))
      (node (ref "AMP_A") (pin "3") (pinfunction "IN3_3") (pintype "input"))
    )
    (net (code "55") (name "Net-(AMP_A-IN4)") (class "Default")
      (node (ref "AIN_BNB") (pin "64") (pinfunction "64_64") (pintype "bidirectional"))
      (node (ref "AMP_A") (pin "4") (pinfunction "IN4_4") (pintype "input"))
    )
    (net (code "56") (name "Net-(AMP_A-IN5)") (class "Default")
      (node (ref "AIN_BNB") (pin "63") (pinfunction "63_63") (pintype "bidirectional"))
      (node (ref "AMP_A") (pin "5") (pinfunction "IN5_5") (pintype "input"))
    )
    (net (code "57") (name "Net-(AMP_A-IN6)") (class "Default")
      (node (ref "AIN_BNB") (pin "62") (pinfunction "62_62") (pintype "bidirectional"))
      (node (ref "AMP_A") (pin "6") (pinfunction "IN6_6") (pintype "input"))
    )
    (net (code "58") (name "Net-(AMP_A-IN7)") (class "Default")
      (node (ref "AIN_BNB") (pin "61") (pinfunction "61_61") (pintype "bidirectional"))
      (node (ref "AMP_A") (pin "7") (pinfunction "IN7_7") (pintype "input"))
    )
    (net (code "59") (name "Net-(AMP_A-IN8)") (class "Default")
      (node (ref "AIN_BNB") (pin "60") (pinfunction "60_60") (pintype "bidirectional"))
      (node (ref "AMP_A") (pin "8") (pinfunction "IN8_8") (pintype "input"))
    )
    (net (code "60") (name "Net-(AMP_A-IN9)") (class "Default")
      (node (ref "AIN_BNB") (pin "59") (pinfunction "59_59") (pintype "bidirectional"))
      (node (ref "AMP_A") (pin "9") (pinfunction "IN9_9") (pintype "input"))
    )
    (net (code "61") (name "Net-(AMP_A-IN10)") (class "Default")
      (node (ref "AIN_BNB") (pin "58") (pinfunction "58_58") (pintype "bidirectional"))
      (node (ref "AMP_A") (pin "10") (pinfunction "IN10_10") (pintype "input"))
    )
    (net (code "62") (name "Net-(AMP_A-IN11)") (class "Default")
      (node (ref "AIN_BNB") (pin "57") (pinfunction "57_57") (pintype "bidirectional"))
      (node (ref "AMP_A") (pin "11") (pinfunction "IN11_11") (pintype "input"))
    )
    (net (code "63") (name "Net-(AMP_A-IN12)") (class "Default")
      (node (ref "AIN_BNB") (pin "56") (pinfunction "56_56") (pintype "bidirectional"))
      (node (ref "AMP_A") (pin "12") (pinfunction "IN12_12") (pintype "input"))
    )
    (net (code "64") (name "Net-(AMP_A-IN13)") (class "Default")
      (node (ref "AIN_BNB") (pin "55") (pinfunction "55_55") (pintype "bidirectional"))
      (node (ref "AMP_A") (pin "13") (pinfunction "IN13_13") (pintype "input"))
    )
    (net (code "65") (name "Net-(AMP_A-IN14)") (class "Default")
      (node (ref "AIN_BNB") (pin "54") (pinfunction "54_54") (pintype "bidirectional"))
      (node (ref "AMP_A") (pin "14") (pinfunction "IN14_14") (pintype "input"))
    )
    (net (code "66") (name "Net-(AMP_A-IN15)") (class "Default")
      (node (ref "AIN_BNB") (pin "53") (pinfunction "53_53") (pintype "bidirectional"))
      (node (ref "AMP_A") (pin "15") (pinfunction "IN15_15") (pintype "input"))
    )
    (net (code "67") (name "Net-(AMP_A-IN16)") (class "Default")
      (node (ref "AIN_BNB") (pin "52") (pinfunction "52_52") (pintype "bidirectional"))
      (node (ref "AMP_A") (pin "16") (pinfunction "IN16_16") (pintype "input"))
    )
    (net (code "68") (name "Net-(AMP_A-IN17)") (class "Default")
      (node (ref "AIN_BNB") (pin "51") (pinfunction "51_51") (pintype "bidirectional"))
      (node (ref "AMP_A") (pin "17") (pinfunction "IN17_17") (pintype "input"))
    )
    (net (code "69") (name "Net-(AMP_A-IN18)") (class "Default")
      (node (ref "AIN_BNB") (pin "50") (pinfunction "50_50") (pintype "bidirectional"))
      (node (ref "AMP_A") (pin "18") (pinfunction "IN18_18") (pintype "input"))
    )
    (net (code "70") (name "Net-(AMP_A-IN19)") (class "Default")
      (node (ref "AIN_BNB") (pin "49") (pinfunction "49_49") (pintype "bidirectional"))
      (node (ref "AMP_A") (pin "19") (pinfunction "IN19_19") (pintype "input"))
    )
    (net (code "71") (name "Net-(AMP_A-IN20)") (class "Default")
      (node (ref "AIN_BNB") (pin "48") (pinfunction "48_48") (pintype "bidirectional"))
      (node (ref "AMP_A") (pin "20") (pinfunction "IN20_20") (pintype "input"))
    )
    (net (code "72") (name "Net-(AMP_A-IN21)") (class "Default")
      (node (ref "AIN_BNB") (pin "47") (pinfunction "47_47") (pintype "bidirectional"))
      (node (ref "AMP_A") (pin "21") (pinfunction "IN21_21") (pintype "input"))
    )
    (net (code "73") (name "Net-(AMP_A-IN22)") (class "Default")
      (node (ref "AIN_BNB") (pin "46") (pinfunction "46_46") (pintype "bidirectional"))
      (node (ref "AMP_A") (pin "22") (pinfunction "IN22_22") (pintype "input"))
    )
    (net (code "74") (name "Net-(AMP_A-IN23)") (class "Default")
      (node (ref "AIN_BNB") (pin "45") (pinfunction "45_45") (pintype "bidirectional"))
      (node (ref "AMP_A") (pin "23") (pinfunction "IN23_23") (pintype "input"))
    )
    (net (code "75") (name "Net-(AMP_A-IN24)") (class "Default")
      (node (ref "AIN_BNB") (pin "44") (pinfunction "44_44") (pintype "bidirectional"))
      (node (ref "AMP_A") (pin "24") (pinfunction "IN24_24") (pintype "input"))
    )
    (net (code "76") (name "Net-(AMP_A-IN25)") (class "Default")
      (node (ref "AIN_BNB") (pin "43") (pinfunction "43_43") (pintype "bidirectional"))
      (node (ref "AMP_A") (pin "25") (pinfunction "IN25_25") (pintype "input"))
    )
    (net (code "77") (name "Net-(AMP_A-IN26)") (class "Default")
      (node (ref "AIN_BNB") (pin "42") (pinfunction "42_42") (pintype "bidirectional"))
      (node (ref "AMP_A") (pin "26") (pinfunction "IN26_26") (pintype "input"))
    )
    (net (code "78") (name "Net-(AMP_A-IN27)") (class "Default")
      (node (ref "AIN_BNB") (pin "41") (pinfunction "41_41") (pintype "bidirectional"))
      (node (ref "AMP_A") (pin "27") (pinfunction "IN27_27") (pintype "input"))
    )
    (net (code "79") (name "Net-(AMP_A-IN28)") (class "Default")
      (node (ref "AIN_BNB") (pin "40") (pinfunction "40_40") (pintype "bidirectional"))
      (node (ref "AMP_A") (pin "28") (pinfunction "IN28_28") (pintype "input"))
    )
    (net (code "80") (name "Net-(AMP_A-IN29)") (class "Default")
      (node (ref "AIN_BNB") (pin "39") (pinfunction "39_39") (pintype "bidirectional"))
      (node (ref "AMP_A") (pin "29") (pinfunction "IN29_29") (pintype "input"))
    )
    (net (code "81") (name "Net-(AMP_A-IN30)") (class "Default")
      (node (ref "AIN_BNB") (pin "38") (pinfunction "38_38") (pintype "bidirectional"))
      (node (ref "AMP_A") (pin "30") (pinfunction "IN30_30") (pintype "input"))
    )
    (net (code "82") (name "Net-(AMP_A-IN31)") (class "Default")
      (node (ref "AIN_BNB") (pin "37") (pinfunction "37_37") (pintype "bidirectional"))
      (node (ref "AMP_A") (pin "31") (pinfunction "IN31_31") (pintype "input"))
    )
    (net (code "83") (name "Net-(AMP_A-IN32)") (class "Default")
      (node (ref "AIN_BNB") (pin "33") (pinfunction "33_33") (pintype "bidirectional"))
      (node (ref "AMP_A") (pin "32") (pinfunction "IN32_32") (pintype "input"))
    )
    (net (code "84") (name "Net-(AMP_A-IN33)") (class "Default")
      (node (ref "AIN_BNB") (pin "32") (pinfunction "32_32") (pintype "bidirectional"))
      (node (ref "AMP_A") (pin "33") (pinfunction "IN33_33") (pintype "input"))
    )
    (net (code "85") (name "Net-(AMP_A-IN34)") (class "Default")
      (node (ref "AIN_BNB") (pin "31") (pinfunction "31_31") (pintype "bidirectional"))
      (node (ref "AMP_A") (pin "34") (pinfunction "IN34_34") (pintype "input"))
    )
    (net (code "86") (name "Net-(AMP_A-IN35)") (class "Default")
      (node (ref "AIN_BNB") (pin "30") (pinfunction "30_30") (pintype "bidirectional"))
      (node (ref "AMP_A") (pin "35") (pinfunction "IN35_35") (pintype "input"))
    )
    (net (code "87") (name "Net-(AMP_A-IN36)") (class "Default")
      (node (ref "AIN_BNB") (pin "29") (pinfunction "29_29") (pintype "bidirectional"))
      (node (ref "AMP_A") (pin "36") (pinfunction "IN36_36") (pintype "input"))
    )
    (net (code "88") (name "Net-(AMP_A-IN37)") (class "Default")
      (node (ref "AIN_BNB") (pin "28") (pinfunction "28_28") (pintype "bidirectional"))
      (node (ref "AMP_A") (pin "37") (pinfunction "IN37_37") (pintype "input"))
    )
    (net (code "89") (name "Net-(AMP_A-IN38)") (class "Default")
      (node (ref "AIN_BNB") (pin "27") (pinfunction "27_27") (pintype "bidirectional"))
      (node (ref "AMP_A") (pin "38") (pinfunction "IN38_38") (pintype "input"))
    )
    (net (code "90") (name "Net-(AMP_A-IN39)") (class "Default")
      (node (ref "AIN_BNB") (pin "26") (pinfunction "26_26") (pintype "bidirectional"))
      (node (ref "AMP_A") (pin "39") (pinfunction "IN39_39") (pintype "input"))
    )
    (net (code "91") (name "Net-(AMP_A-IN40)") (class "Default")
      (node (ref "AIN_BNB") (pin "25") (pinfunction "25_25") (pintype "bidirectional"))
      (node (ref "AMP_A") (pin "40") (pinfunction "IN40_40") (pintype "input"))
    )
    (net (code "92") (name "Net-(AMP_A-IN41)") (class "Default")
      (node (ref "AIN_BNB") (pin "24") (pinfunction "24_24") (pintype "bidirectional"))
      (node (ref "AMP_A") (pin "41") (pinfunction "IN41_41") (pintype "input"))
    )
    (net (code "93") (name "Net-(AMP_A-IN42)") (class "Default")
      (node (ref "AIN_BNB") (pin "23") (pinfunction "23_23") (pintype "bidirectional"))
      (node (ref "AMP_A") (pin "42") (pinfunction "IN42_42") (pintype "input"))
    )
    (net (code "94") (name "Net-(AMP_A-IN43)") (class "Default")
      (node (ref "AIN_BNB") (pin "22") (pinfunction "22_22") (pintype "bidirectional"))
      (node (ref "AMP_A") (pin "43") (pinfunction "IN43_43") (pintype "input"))
    )
    (net (code "95") (name "Net-(AMP_A-IN44)") (class "Default")
      (node (ref "AIN_BNB") (pin "21") (pinfunction "21_21") (pintype "bidirectional"))
      (node (ref "AMP_A") (pin "44") (pinfunction "IN44_44") (pintype "input"))
    )
    (net (code "96") (name "Net-(AMP_A-IN45)") (class "Default")
      (node (ref "AIN_BNB") (pin "20") (pinfunction "20_20") (pintype "bidirectional"))
      (node (ref "AMP_A") (pin "45") (pinfunction "IN45_45") (pintype "input"))
    )
    (net (code "97") (name "Net-(AMP_A-IN46)") (class "Default")
      (node (ref "AIN_BNB") (pin "19") (pinfunction "19_19") (pintype "bidirectional"))
      (node (ref "AMP_A") (pin "46") (pinfunction "IN46_46") (pintype "input"))
    )
    (net (code "98") (name "Net-(AMP_A-IN47)") (class "Default")
      (node (ref "AIN_BNB") (pin "18") (pinfunction "18_18") (pintype "bidirectional"))
      (node (ref "AMP_A") (pin "47") (pinfunction "IN47_47") (pintype "input"))
    )
    (net (code "99") (name "Net-(AMP_A-IN48)") (class "Default")
      (node (ref "AIN_BNB") (pin "17") (pinfunction "17_17") (pintype "bidirectional"))
      (node (ref "AMP_A") (pin "48") (pinfunction "IN48_48") (pintype "input"))
    )
    (net (code "100") (name "Net-(AMP_A-IN49)") (class "Default")
      (node (ref "AIN_BNB") (pin "16") (pinfunction "16_16") (pintype "bidirectional"))
      (node (ref "AMP_A") (pin "49") (pinfunction "IN49_49") (pintype "input"))
    )
    (net (code "101") (name "Net-(AMP_A-IN50)") (class "Default")
      (node (ref "AIN_BNB") (pin "15") (pinfunction "15_15") (pintype "bidirectional"))
      (node (ref "AMP_A") (pin "50") (pinfunction "IN50_50") (pintype "input"))
    )
    (net (code "102") (name "Net-(AMP_A-IN51)") (class "Default")
      (node (ref "AIN_BNB") (pin "14") (pinfunction "14_14") (pintype "bidirectional"))
      (node (ref "AMP_A") (pin "51") (pinfunction "IN51_51") (pintype "input"))
    )
    (net (code "103") (name "Net-(AMP_A-IN52)") (class "Default")
      (node (ref "AIN_BNB") (pin "13") (pinfunction "13_13") (pintype "bidirectional"))
      (node (ref "AMP_A") (pin "52") (pinfunction "IN52_52") (pintype "input"))
    )
    (net (code "104") (name "Net-(AMP_A-IN53)") (class "Default")
      (node (ref "AIN_BNB") (pin "12") (pinfunction "12_12") (pintype "bidirectional"))
      (node (ref "AMP_A") (pin "53") (pinfunction "IN53_53") (pintype "input"))
    )
    (net (code "105") (name "Net-(AMP_A-IN54)") (class "Default")
      (node (ref "AIN_BNB") (pin "11") (pinfunction "11_11") (pintype "bidirectional"))
      (node (ref "AMP_A") (pin "54") (pinfunction "IN54_54") (pintype "input"))
    )
    (net (code "106") (name "Net-(AMP_A-IN55)") (class "Default")
      (node (ref "AIN_BNB") (pin "10") (pinfunction "10_10") (pintype "bidirectional"))
      (node (ref "AMP_A") (pin "55") (pinfunction "IN55_55") (pintype "input"))
    )
    (net (code "107") (name "Net-(AMP_A-IN56)") (class "Default")
      (node (ref "AIN_BNB") (pin "9") (pinfunction "9_9") (pintype "bidirectional"))
      (node (ref "AMP_A") (pin "56") (pinfunction "IN56_56") (pintype "input"))
    )
    (net (code "108") (name "Net-(AMP_A-IN57)") (class "Default")
      (node (ref "AIN_BNB") (pin "8") (pinfunction "8_8") (pintype "bidirectional"))
      (node (ref "AMP_A") (pin "57") (pinfunction "IN57_57") (pintype "input"))
    )
    (net (code "109") (name "Net-(AMP_A-IN58)") (class "Default")
      (node (ref "AIN_BNB") (pin "7") (pinfunction "7_7") (pintype "bidirectional"))
      (node (ref "AMP_A") (pin "58") (pinfunction "IN58_58") (pintype "input"))
    )
    (net (code "110") (name "Net-(AMP_A-IN59)") (class "Default")
      (node (ref "AIN_BNB") (pin "6") (pinfunction "6_6") (pintype "bidirectional"))
      (node (ref "AMP_A") (pin "59") (pinfunction "IN59_59") (pintype "input"))
    )
    (net (code "111") (name "Net-(AMP_A-IN60)") (class "Default")
      (node (ref "AIN_BNB") (pin "5") (pinfunction "5_5") (pintype "bidirectional"))
      (node (ref "AMP_A") (pin "60") (pinfunction "IN60_60") (pintype "input"))
    )
    (net (code "112") (name "Net-(AMP_A-IN61)") (class "Default")
      (node (ref "AIN_BNB") (pin "4") (pinfunction "4_4") (pintype "bidirectional"))
      (node (ref "AMP_A") (pin "61") (pinfunction "IN61_61") (pintype "input"))
    )
    (net (code "113") (name "Net-(AMP_A-IN62)") (class "Default")
      (node (ref "AIN_BNB") (pin "3") (pinfunction "3_3") (pintype "bidirectional"))
      (node (ref "AMP_A") (pin "62") (pinfunction "IN62_62") (pintype "input"))
    )
    (net (code "114") (name "Net-(AMP_A-IN63)") (class "Default")
      (node (ref "AIN_BNB") (pin "2") (pinfunction "2_2") (pintype "bidirectional"))
      (node (ref "AMP_A") (pin "63") (pinfunction "IN63_63") (pintype "input"))
    )
    (net (code "115") (name "Net-(AMP_B-ADC_REF)") (class "Default")
      (node (ref "AMP_B") (pin "B19") (pinfunction "ADC_REF_B19") (pintype "passive"))
      (node (ref "C7") (pin "1") (pinfunction "1_1") (pintype "passive"))
    )
    (net (code "116") (name "Net-(AMP_B-IN0)") (class "Default")
      (node (ref "AIN_BSB") (pin "68") (pinfunction "68_68") (pintype "bidirectional"))
      (node (ref "AMP_B") (pin "0") (pinfunction "IN0_0") (pintype "input"))
    )
    (net (code "117") (name "Net-(AMP_B-IN1)") (class "Default")
      (node (ref "AIN_BSB") (pin "67") (pinfunction "67_67") (pintype "bidirectional"))
      (node (ref "AMP_B") (pin "1") (pinfunction "IN1_1") (pintype "input"))
    )
    (net (code "118") (name "Net-(AMP_B-IN2)") (class "Default")
      (node (ref "AIN_BSB") (pin "66") (pinfunction "66_66") (pintype "bidirectional"))
      (node (ref "AMP_B") (pin "2") (pinfunction "IN2_2") (pintype "input"))
    )
    (net (code "119") (name "Net-(AMP_B-IN3)") (class "Default")
      (node (ref "AIN_BSB") (pin "65") (pinfunction "65_65") (pintype "bidirectional"))
      (node (ref "AMP_B") (pin "3") (pinfunction "IN3_3") (pintype "input"))
    )
    (net (code "120") (name "Net-(AMP_B-IN4)") (class "Default")
      (node (ref "AIN_BSB") (pin "64") (pinfunction "64_64") (pintype "bidirectional"))
      (node (ref "AMP_B") (pin "4") (pinfunction "IN4_4") (pintype "input"))
    )
    (net (code "121") (name "Net-(AMP_B-IN5)") (class "Default")
      (node (ref "AIN_BSB") (pin "63") (pinfunction "63_63") (pintype "bidirectional"))
      (node (ref "AMP_B") (pin "5") (pinfunction "IN5_5") (pintype "input"))
    )
    (net (code "122") (name "Net-(AMP_B-IN6)") (class "Default")
      (node (ref "AIN_BSB") (pin "62") (pinfunction "62_62") (pintype "bidirectional"))
      (node (ref "AMP_B") (pin "6") (pinfunction "IN6_6") (pintype "input"))
    )
    (net (code "123") (name "Net-(AMP_B-IN7)") (class "Default")
      (node (ref "AIN_BSB") (pin "61") (pinfunction "61_61") (pintype "bidirectional"))
      (node (ref "AMP_B") (pin "7") (pinfunction "IN7_7") (pintype "input"))
    )
    (net (code "124") (name "Net-(AMP_B-IN8)") (class "Default")
      (node (ref "AIN_BSB") (pin "60") (pinfunction "60_60") (pintype "bidirectional"))
      (node (ref "AMP_B") (pin "8") (pinfunction "IN8_8") (pintype "input"))
    )
    (net (code "125") (name "Net-(AMP_B-IN9)") (class "Default")
      (node (ref "AIN_BSB") (pin "59") (pinfunction "59_59") (pintype "bidirectional"))
      (node (ref "AMP_B") (pin "9") (pinfunction "IN9_9") (pintype "input"))
    )
    (net (code "126") (name "Net-(AMP_B-IN10)") (class "Default")
      (node (ref "AIN_BSB") (pin "58") (pinfunction "58_58") (pintype "bidirectional"))
      (node (ref "AMP_B") (pin "10") (pinfunction "IN10_10") (pintype "input"))
    )
    (net (code "127") (name "Net-(AMP_B-IN11)") (class "Default")
      (node (ref "AIN_BSB") (pin "57") (pinfunction "57_57") (pintype "bidirectional"))
      (node (ref "AMP_B") (pin "11") (pinfunction "IN11_11") (pintype "input"))
    )
    (net (code "128") (name "Net-(AMP_B-IN12)") (class "Default")
      (node (ref "AIN_BSB") (pin "56") (pinfunction "56_56") (pintype "bidirectional"))
      (node (ref "AMP_B") (pin "12") (pinfunction "IN12_12") (pintype "input"))
    )
    (net (code "129") (name "Net-(AMP_B-IN13)") (class "Default")
      (node (ref "AIN_BSB") (pin "55") (pinfunction "55_55") (pintype "bidirectional"))
      (node (ref "AMP_B") (pin "13") (pinfunction "IN13_13") (pintype "input"))
    )
    (net (code "130") (name "Net-(AMP_B-IN14)") (class "Default")
      (node (ref "AIN_BSB") (pin "54") (pinfunction "54_54") (pintype "bidirectional"))
      (node (ref "AMP_B") (pin "14") (pinfunction "IN14_14") (pintype "input"))
    )
    (net (code "131") (name "Net-(AMP_B-IN15)") (class "Default")
      (node (ref "AIN_BSB") (pin "53") (pinfunction "53_53") (pintype "bidirectional"))
      (node (ref "AMP_B") (pin "15") (pinfunction "IN15_15") (pintype "input"))
    )
    (net (code "132") (name "Net-(AMP_B-IN16)") (class "Default")
      (node (ref "AIN_BSB") (pin "52") (pinfunction "52_52") (pintype "bidirectional"))
      (node (ref "AMP_B") (pin "16") (pinfunction "IN16_16") (pintype "input"))
    )
    (net (code "133") (name "Net-(AMP_B-IN17)") (class "Default")
      (node (ref "AIN_BSB") (pin "51") (pinfunction "51_51") (pintype "bidirectional"))
      (node (ref "AMP_B") (pin "17") (pinfunction "IN17_17") (pintype "input"))
    )
    (net (code "134") (name "Net-(AMP_B-IN18)") (class "Default")
      (node (ref "AIN_BSB") (pin "50") (pinfunction "50_50") (pintype "bidirectional"))
      (node (ref "AMP_B") (pin "18") (pinfunction "IN18_18") (pintype "input"))
    )
    (net (code "135") (name "Net-(AMP_B-IN19)") (class "Default")
      (node (ref "AIN_BSB") (pin "49") (pinfunction "49_49") (pintype "bidirectional"))
      (node (ref "AMP_B") (pin "19") (pinfunction "IN19_19") (pintype "input"))
    )
    (net (code "136") (name "Net-(AMP_B-IN20)") (class "Default")
      (node (ref "AIN_BSB") (pin "48") (pinfunction "48_48") (pintype "bidirectional"))
      (node (ref "AMP_B") (pin "20") (pinfunction "IN20_20") (pintype "input"))
    )
    (net (code "137") (name "Net-(AMP_B-IN21)") (class "Default")
      (node (ref "AIN_BSB") (pin "47") (pinfunction "47_47") (pintype "bidirectional"))
      (node (ref "AMP_B") (pin "21") (pinfunction "IN21_21") (pintype "input"))
    )
    (net (code "138") (name "Net-(AMP_B-IN22)") (class "Default")
      (node (ref "AIN_BSB") (pin "46") (pinfunction "46_46") (pintype "bidirectional"))
      (node (ref "AMP_B") (pin "22") (pinfunction "IN22_22") (pintype "input"))
    )
    (net (code "139") (name "Net-(AMP_B-IN23)") (class "Default")
      (node (ref "AIN_BSB") (pin "45") (pinfunction "45_45") (pintype "bidirectional"))
      (node (ref "AMP_B") (pin "23") (pinfunction "IN23_23") (pintype "input"))
    )
    (net (code "140") (name "Net-(AMP_B-IN24)") (class "Default")
      (node (ref "AIN_BSB") (pin "44") (pinfunction "44_44") (pintype "bidirectional"))
      (node (ref "AMP_B") (pin "24") (pinfunction "IN24_24") (pintype "input"))
    )
    (net (code "141") (name "Net-(AMP_B-IN25)") (class "Default")
      (node (ref "AIN_BSB") (pin "43") (pinfunction "43_43") (pintype "bidirectional"))
      (node (ref "AMP_B") (pin "25") (pinfunction "IN25_25") (pintype "input"))
    )
    (net (code "142") (name "Net-(AMP_B-IN26)") (class "Default")
      (node (ref "AIN_BSB") (pin "42") (pinfunction "42_42") (pintype "bidirectional"))
      (node (ref "AMP_B") (pin "26") (pinfunction "IN26_26") (pintype "input"))
    )
    (net (code "143") (name "Net-(AMP_B-IN27)") (class "Default")
      (node (ref "AIN_BSB") (pin "41") (pinfunction "41_41") (pintype "bidirectional"))
      (node (ref "AMP_B") (pin "27") (pinfunction "IN27_27") (pintype "input"))
    )
    (net (code "144") (name "Net-(AMP_B-IN28)") (class "Default")
      (node (ref "AIN_BSB") (pin "40") (pinfunction "40_40") (pintype "bidirectional"))
      (node (ref "AMP_B") (pin "28") (pinfunction "IN28_28") (pintype "input"))
    )
    (net (code "145") (name "Net-(AMP_B-IN29)") (class "Default")
      (node (ref "AIN_BSB") (pin "39") (pinfunction "39_39") (pintype "bidirectional"))
      (node (ref "AMP_B") (pin "29") (pinfunction "IN29_29") (pintype "input"))
    )
    (net (code "146") (name "Net-(AMP_B-IN30)") (class "Default")
      (node (ref "AIN_BSB") (pin "38") (pinfunction "38_38") (pintype "bidirectional"))
      (node (ref "AMP_B") (pin "30") (pinfunction "IN30_30") (pintype "input"))
    )
    (net (code "147") (name "Net-(AMP_B-IN31)") (class "Default")
      (node (ref "AIN_BSB") (pin "37") (pinfunction "37_37") (pintype "bidirectional"))
      (node (ref "AMP_B") (pin "31") (pinfunction "IN31_31") (pintype "input"))
    )
    (net (code "148") (name "Net-(AMP_B-IN32)") (class "Default")
      (node (ref "AIN_BSB") (pin "33") (pinfunction "33_33") (pintype "bidirectional"))
      (node (ref "AMP_B") (pin "32") (pinfunction "IN32_32") (pintype "input"))
    )
    (net (code "149") (name "Net-(AMP_B-IN33)") (class "Default")
      (node (ref "AIN_BSB") (pin "32") (pinfunction "32_32") (pintype "bidirectional"))
      (node (ref "AMP_B") (pin "33") (pinfunction "IN33_33") (pintype "input"))
    )
    (net (code "150") (name "Net-(AMP_B-IN34)") (class "Default")
      (node (ref "AIN_BSB") (pin "31") (pinfunction "31_31") (pintype "bidirectional"))
      (node (ref "AMP_B") (pin "34") (pinfunction "IN34_34") (pintype "input"))
    )
    (net (code "151") (name "Net-(AMP_B-IN35)") (class "Default")
      (node (ref "AIN_BSB") (pin "30") (pinfunction "30_30") (pintype "bidirectional"))
      (node (ref "AMP_B") (pin "35") (pinfunction "IN35_35") (pintype "input"))
    )
    (net (code "152") (name "Net-(AMP_B-IN36)") (class "Default")
      (node (ref "AIN_BSB") (pin "29") (pinfunction "29_29") (pintype "bidirectional"))
      (node (ref "AMP_B") (pin "36") (pinfunction "IN36_36") (pintype "input"))
    )
    (net (code "153") (name "Net-(AMP_B-IN37)") (class "Default")
      (node (ref "AIN_BSB") (pin "28") (pinfunction "28_28") (pintype "bidirectional"))
      (node (ref "AMP_B") (pin "37") (pinfunction "IN37_37") (pintype "input"))
    )
    (net (code "154") (name "Net-(AMP_B-IN38)") (class "Default")
      (node (ref "AIN_BSB") (pin "27") (pinfunction "27_27") (pintype "bidirectional"))
      (node (ref "AMP_B") (pin "38") (pinfunction "IN38_38") (pintype "input"))
    )
    (net (code "155") (name "Net-(AMP_B-IN39)") (class "Default")
      (node (ref "AIN_BSB") (pin "26") (pinfunction "26_26") (pintype "bidirectional"))
      (node (ref "AMP_B") (pin "39") (pinfunction "IN39_39") (pintype "input"))
    )
    (net (code "156") (name "Net-(AMP_B-IN40)") (class "Default")
      (node (ref "AIN_BSB") (pin "25") (pinfunction "25_25") (pintype "bidirectional"))
      (node (ref "AMP_B") (pin "40") (pinfunction "IN40_40") (pintype "input"))
    )
    (net (code "157") (name "Net-(AMP_B-IN41)") (class "Default")
      (node (ref "AIN_BSB") (pin "24") (pinfunction "24_24") (pintype "bidirectional"))
      (node (ref "AMP_B") (pin "41") (pinfunction "IN41_41") (pintype "input"))
    )
    (net (code "158") (name "Net-(AMP_B-IN42)") (class "Default")
      (node (ref "AIN_BSB") (pin "23") (pinfunction "23_23") (pintype "bidirectional"))
      (node (ref "AMP_B") (pin "42") (pinfunction "IN42_42") (pintype "input"))
    )
    (net (code "159") (name "Net-(AMP_B-IN43)") (class "Default")
      (node (ref "AIN_BSB") (pin "22") (pinfunction "22_22") (pintype "bidirectional"))
      (node (ref "AMP_B") (pin "43") (pinfunction "IN43_43") (pintype "input"))
    )
    (net (code "160") (name "Net-(AMP_B-IN44)") (class "Default")
      (node (ref "AIN_BSB") (pin "21") (pinfunction "21_21") (pintype "bidirectional"))
      (node (ref "AMP_B") (pin "44") (pinfunction "IN44_44") (pintype "input"))
    )
    (net (code "161") (name "Net-(AMP_B-IN45)") (class "Default")
      (node (ref "AIN_BSB") (pin "20") (pinfunction "20_20") (pintype "bidirectional"))
      (node (ref "AMP_B") (pin "45") (pinfunction "IN45_45") (pintype "input"))
    )
    (net (code "162") (name "Net-(AMP_B-IN46)") (class "Default")
      (node (ref "AIN_BSB") (pin "19") (pinfunction "19_19") (pintype "bidirectional"))
      (node (ref "AMP_B") (pin "46") (pinfunction "IN46_46") (pintype "input"))
    )
    (net (code "163") (name "Net-(AMP_B-IN47)") (class "Default")
      (node (ref "AIN_BSB") (pin "18") (pinfunction "18_18") (pintype "bidirectional"))
      (node (ref "AMP_B") (pin "47") (pinfunction "IN47_47") (pintype "input"))
    )
    (net (code "164") (name "Net-(AMP_B-IN48)") (class "Default")
      (node (ref "AIN_BSB") (pin "17") (pinfunction "17_17") (pintype "bidirectional"))
      (node (ref "AMP_B") (pin "48") (pinfunction "IN48_48") (pintype "input"))
    )
    (net (code "165") (name "Net-(AMP_B-IN49)") (class "Default")
      (node (ref "AIN_BSB") (pin "16") (pinfunction "16_16") (pintype "bidirectional"))
      (node (ref "AMP_B") (pin "49") (pinfunction "IN49_49") (pintype "input"))
    )
    (net (code "166") (name "Net-(AMP_B-IN50)") (class "Default")
      (node (ref "AIN_BSB") (pin "15") (pinfunction "15_15") (pintype "bidirectional"))
      (node (ref "AMP_B") (pin "50") (pinfunction "IN50_50") (pintype "input"))
    )
    (net (code "167") (name "Net-(AMP_B-IN51)") (class "Default")
      (node (ref "AIN_BSB") (pin "14") (pinfunction "14_14") (pintype "bidirectional"))
      (node (ref "AMP_B") (pin "51") (pinfunction "IN51_51") (pintype "input"))
    )
    (net (code "168") (name "Net-(AMP_B-IN52)") (class "Default")
      (node (ref "AIN_BSB") (pin "13") (pinfunction "13_13") (pintype "bidirectional"))
      (node (ref "AMP_B") (pin "52") (pinfunction "IN52_52") (pintype "input"))
    )
    (net (code "169") (name "Net-(AMP_B-IN53)") (class "Default")
      (node (ref "AIN_BSB") (pin "12") (pinfunction "12_12") (pintype "bidirectional"))
      (node (ref "AMP_B") (pin "53") (pinfunction "IN53_53") (pintype "input"))
    )
    (net (code "170") (name "Net-(AMP_B-IN54)") (class "Default")
      (node (ref "AIN_BSB") (pin "11") (pinfunction "11_11") (pintype "bidirectional"))
      (node (ref "AMP_B") (pin "54") (pinfunction "IN54_54") (pintype "input"))
    )
    (net (code "171") (name "Net-(AMP_B-IN55)") (class "Default")
      (node (ref "AIN_BSB") (pin "10") (pinfunction "10_10") (pintype "bidirectional"))
      (node (ref "AMP_B") (pin "55") (pinfunction "IN55_55") (pintype "input"))
    )
    (net (code "172") (name "Net-(AMP_B-IN56)") (class "Default")
      (node (ref "AIN_BSB") (pin "9") (pinfunction "9_9") (pintype "bidirectional"))
      (node (ref "AMP_B") (pin "56") (pinfunction "IN56_56") (pintype "input"))
    )
    (net (code "173") (name "Net-(AMP_B-IN57)") (class "Default")
      (node (ref "AIN_BSB") (pin "8") (pinfunction "8_8") (pintype "bidirectional"))
      (node (ref "AMP_B") (pin "57") (pinfunction "IN57_57") (pintype "input"))
    )
    (net (code "174") (name "Net-(AMP_B-IN58)") (class "Default")
      (node (ref "AIN_BSB") (pin "7") (pinfunction "7_7") (pintype "bidirectional"))
      (node (ref "AMP_B") (pin "58") (pinfunction "IN58_58") (pintype "input"))
    )
    (net (code "175") (name "Net-(AMP_B-IN59)") (class "Default")
      (node (ref "AIN_BSB") (pin "6") (pinfunction "6_6") (pintype "bidirectional"))
      (node (ref "AMP_B") (pin "59") (pinfunction "IN59_59") (pintype "input"))
    )
    (net (code "176") (name "Net-(AMP_B-IN60)") (class "Default")
      (node (ref "AIN_BSB") (pin "5") (pinfunction "5_5") (pintype "bidirectional"))
      (node (ref "AMP_B") (pin "60") (pinfunction "IN60_60") (pintype "input"))
    )
    (net (code "177") (name "Net-(AMP_B-IN61)") (class "Default")
      (node (ref "AIN_BSB") (pin "4") (pinfunction "4_4") (pintype "bidirectional"))
      (node (ref "AMP_B") (pin "61") (pinfunction "IN61_61") (pintype "input"))
    )
    (net (code "178") (name "Net-(AMP_B-IN62)") (class "Default")
      (node (ref "AIN_BSB") (pin "3") (pinfunction "3_3") (pintype "bidirectional"))
      (node (ref "AMP_B") (pin "62") (pinfunction "IN62_62") (pintype "input"))
    )
    (net (code "179") (name "Net-(AMP_B-IN63)") (class "Default")
      (node (ref "AIN_BSB") (pin "2") (pinfunction "2_2") (pintype "bidirectional"))
      (node (ref "AMP_B") (pin "63") (pinfunction "IN63_63") (pintype "input"))
    )
    (net (code "180") (name "Net-(ATHRU_BEB-Pad2)") (class "Default")
      (node (ref "ATHRU_BEB") (pin "2") (pinfunction "2_2") (pintype "bidirectional"))
      (node (ref "ATHRU_TEB") (pin "2") (pinfunction "2_2") (pintype "bidirectional"))
    )
    (net (code "181") (name "Net-(ATHRU_BEB-Pad3)") (class "Default")
      (node (ref "ATHRU_BEB") (pin "3") (pinfunction "3_3") (pintype "bidirectional"))
      (node (ref "ATHRU_TEB") (pin "3") (pinfunction "3_3") (pintype "bidirectional"))
    )
    (net (code "182") (name "Net-(ATHRU_BEB-Pad4)") (class "Default")
      (node (ref "ATHRU_BEB") (pin "4") (pinfunction "4_4") (pintype "bidirectional"))
      (node (ref "ATHRU_TEB") (pin "4") (pinfunction "4_4") (pintype "bidirectional"))
    )
    (net (code "183") (name "Net-(ATHRU_BEB-Pad5)") (class "Default")
      (node (ref "ATHRU_BEB") (pin "5") (pinfunction "5_5") (pintype "bidirectional"))
      (node (ref "ATHRU_TEB") (pin "5") (pinfunction "5_5") (pintype "bidirectional"))
    )
    (net (code "184") (name "Net-(ATHRU_BEB-Pad6)") (class "Default")
      (node (ref "ATHRU_BEB") (pin "6") (pinfunction "6_6") (pintype "bidirectional"))
      (node (ref "ATHRU_TEB") (pin "6") (pinfunction "6_6") (pintype "bidirectional"))
    )
    (net (code "185") (name "Net-(ATHRU_BEB-Pad7)") (class "Default")
      (node (ref "ATHRU_BEB") (pin "7") (pinfunction "7_7") (pintype "bidirectional"))
      (node (ref "ATHRU_TEB") (pin "7") (pinfunction "7_7") (pintype "bidirectional"))
    )
    (net (code "186") (name "Net-(ATHRU_BEB-Pad8)") (class "Default")
      (node (ref "ATHRU_BEB") (pin "8") (pinfunction "8_8") (pintype "bidirectional"))
      (node (ref "ATHRU_TEB") (pin "8") (pinfunction "8_8") (pintype "bidirectional"))
    )
    (net (code "187") (name "Net-(ATHRU_BEB-Pad9)") (class "Default")
      (node (ref "ATHRU_BEB") (pin "9") (pinfunction "9_9") (pintype "bidirectional"))
      (node (ref "ATHRU_TEB") (pin "9") (pinfunction "9_9") (pintype "bidirectional"))
    )
    (net (code "188") (name "Net-(ATHRU_BEB-Pad10)") (class "Default")
      (node (ref "ATHRU_BEB") (pin "10") (pinfunction "10_10") (pintype "bidirectional"))
      (node (ref "ATHRU_TEB") (pin "10") (pinfunction "10_10") (pintype "bidirectional"))
    )
    (net (code "189") (name "Net-(ATHRU_BEB-Pad11)") (class "Default")
      (node (ref "ATHRU_BEB") (pin "11") (pinfunction "11_11") (pintype "bidirectional"))
      (node (ref "ATHRU_TEB") (pin "11") (pinfunction "11_11") (pintype "bidirectional"))
    )
    (net (code "190") (name "Net-(ATHRU_BEB-Pad12)") (class "Default")
      (node (ref "ATHRU_BEB") (pin "12") (pinfunction "12_12") (pintype "bidirectional"))
      (node (ref "ATHRU_TEB") (pin "12") (pinfunction "12_12") (pintype "bidirectional"))
    )
    (net (code "191") (name "Net-(ATHRU_BEB-Pad13)") (class "Default")
      (node (ref "ATHRU_BEB") (pin "13") (pinfunction "13_13") (pintype "bidirectional"))
      (node (ref "ATHRU_TEB") (pin "13") (pinfunction "13_13") (pintype "bidirectional"))
    )
    (net (code "192") (name "Net-(ATHRU_BEB-Pad14)") (class "Default")
      (node (ref "ATHRU_BEB") (pin "14") (pinfunction "14_14") (pintype "bidirectional"))
      (node (ref "ATHRU_TEB") (pin "14") (pinfunction "14_14") (pintype "bidirectional"))
    )
    (net (code "193") (name "Net-(ATHRU_BEB-Pad15)") (class "Default")
      (node (ref "ATHRU_BEB") (pin "15") (pinfunction "15_15") (pintype "bidirectional"))
      (node (ref "ATHRU_TEB") (pin "15") (pinfunction "15_15") (pintype "bidirectional"))
    )
    (net (code "194") (name "Net-(ATHRU_BEB-Pad16)") (class "Default")
      (node (ref "ATHRU_BEB") (pin "16") (pinfunction "16_16") (pintype "bidirectional"))
      (node (ref "ATHRU_TEB") (pin "16") (pinfunction "16_16") (pintype "bidirectional"))
    )
    (net (code "195") (name "Net-(ATHRU_BEB-Pad17)") (class "Default")
      (node (ref "ATHRU_BEB") (pin "17") (pinfunction "17_17") (pintype "bidirectional"))
      (node (ref "ATHRU_TEB") (pin "17") (pinfunction "17_17") (pintype "bidirectional"))
    )
    (net (code "196") (name "Net-(ATHRU_BEB-Pad18)") (class "Default")
      (node (ref "ATHRU_BEB") (pin "18") (pinfunction "18_18") (pintype "bidirectional"))
      (node (ref "ATHRU_TEB") (pin "18") (pinfunction "18_18") (pintype "bidirectional"))
    )
    (net (code "197") (name "Net-(ATHRU_BEB-Pad19)") (class "Default")
      (node (ref "ATHRU_BEB") (pin "19") (pinfunction "19_19") (pintype "bidirectional"))
      (node (ref "ATHRU_TEB") (pin "19") (pinfunction "19_19") (pintype "bidirectional"))
    )
    (net (code "198") (name "Net-(ATHRU_BEB-Pad20)") (class "Default")
      (node (ref "ATHRU_BEB") (pin "20") (pinfunction "20_20") (pintype "bidirectional"))
      (node (ref "ATHRU_TEB") (pin "20") (pinfunction "20_20") (pintype "bidirectional"))
    )
    (net (code "199") (name "Net-(ATHRU_BEB-Pad21)") (class "Default")
      (node (ref "ATHRU_BEB") (pin "21") (pinfunction "21_21") (pintype "bidirectional"))
      (node (ref "ATHRU_TEB") (pin "21") (pinfunction "21_21") (pintype "bidirectional"))
    )
    (net (code "200") (name "Net-(ATHRU_BEB-Pad22)") (class "Default")
      (node (ref "ATHRU_BEB") (pin "22") (pinfunction "22_22") (pintype "bidirectional"))
      (node (ref "ATHRU_TEB") (pin "22") (pinfunction "22_22") (pintype "bidirectional"))
    )
    (net (code "201") (name "Net-(ATHRU_BEB-Pad23)") (class "Default")
      (node (ref "ATHRU_BEB") (pin "23") (pinfunction "23_23") (pintype "bidirectional"))
      (node (ref "ATHRU_TEB") (pin "23") (pinfunction "23_23") (pintype "bidirectional"))
    )
    (net (code "202") (name "Net-(ATHRU_BEB-Pad24)") (class "Default")
      (node (ref "ATHRU_BEB") (pin "24") (pinfunction "24_24") (pintype "bidirectional"))
      (node (ref "ATHRU_TEB") (pin "24") (pinfunction "24_24") (pintype "bidirectional"))
    )
    (net (code "203") (name "Net-(ATHRU_BEB-Pad25)") (class "Default")
      (node (ref "ATHRU_BEB") (pin "25") (pinfunction "25_25") (pintype "bidirectional"))
      (node (ref "ATHRU_TEB") (pin "25") (pinfunction "25_25") (pintype "bidirectional"))
    )
    (net (code "204") (name "Net-(ATHRU_BEB-Pad26)") (class "Default")
      (node (ref "ATHRU_BEB") (pin "26") (pinfunction "26_26") (pintype "bidirectional"))
      (node (ref "ATHRU_TEB") (pin "26") (pinfunction "26_26") (pintype "bidirectional"))
    )
    (net (code "205") (name "Net-(ATHRU_BEB-Pad27)") (class "Default")
      (node (ref "ATHRU_BEB") (pin "27") (pinfunction "27_27") (pintype "bidirectional"))
      (node (ref "ATHRU_TEB") (pin "27") (pinfunction "27_27") (pintype "bidirectional"))
    )
    (net (code "206") (name "Net-(ATHRU_BEB-Pad28)") (class "Default")
      (node (ref "ATHRU_BEB") (pin "28") (pinfunction "28_28") (pintype "bidirectional"))
      (node (ref "ATHRU_TEB") (pin "28") (pinfunction "28_28") (pintype "bidirectional"))
    )
    (net (code "207") (name "Net-(ATHRU_BEB-Pad29)") (class "Default")
      (node (ref "ATHRU_BEB") (pin "29") (pinfunction "29_29") (pintype "bidirectional"))
      (node (ref "ATHRU_TEB") (pin "29") (pinfunction "29_29") (pintype "bidirectional"))
    )
    (net (code "208") (name "Net-(ATHRU_BEB-Pad30)") (class "Default")
      (node (ref "ATHRU_BEB") (pin "30") (pinfunction "30_30") (pintype "bidirectional"))
      (node (ref "ATHRU_TEB") (pin "30") (pinfunction "30_30") (pintype "bidirectional"))
    )
    (net (code "209") (name "Net-(ATHRU_BEB-Pad31)") (class "Default")
      (node (ref "ATHRU_BEB") (pin "31") (pinfunction "31_31") (pintype "bidirectional"))
      (node (ref "ATHRU_TEB") (pin "31") (pinfunction "31_31") (pintype "bidirectional"))
    )
    (net (code "210") (name "Net-(ATHRU_BEB-Pad32)") (class "Default")
      (node (ref "ATHRU_BEB") (pin "32") (pinfunction "32_32") (pintype "bidirectional"))
      (node (ref "ATHRU_TEB") (pin "32") (pinfunction "32_32") (pintype "bidirectional"))
    )
    (net (code "211") (name "Net-(ATHRU_BEB-Pad33)") (class "Default")
      (node (ref "ATHRU_BEB") (pin "33") (pinfunction "33_33") (pintype "bidirectional"))
      (node (ref "ATHRU_TEB") (pin "33") (pinfunction "33_33") (pintype "bidirectional"))
    )
    (net (code "212") (name "Net-(ATHRU_BEB-Pad37)") (class "Default")
      (node (ref "ATHRU_BEB") (pin "37") (pinfunction "37_37") (pintype "bidirectional"))
      (node (ref "ATHRU_TEB") (pin "37") (pinfunction "37_37") (pintype "bidirectional"))
    )
    (net (code "213") (name "Net-(ATHRU_BEB-Pad38)") (class "Default")
      (node (ref "ATHRU_BEB") (pin "38") (pinfunction "38_38") (pintype "bidirectional"))
      (node (ref "ATHRU_TEB") (pin "38") (pinfunction "38_38") (pintype "bidirectional"))
    )
    (net (code "214") (name "Net-(ATHRU_BEB-Pad39)") (class "Default")
      (node (ref "ATHRU_BEB") (pin "39") (pinfunction "39_39") (pintype "bidirectional"))
      (node (ref "ATHRU_TEB") (pin "39") (pinfunction "39_39") (pintype "bidirectional"))
    )
    (net (code "215") (name "Net-(ATHRU_BEB-Pad40)") (class "Default")
      (node (ref "ATHRU_BEB") (pin "40") (pinfunction "40_40") (pintype "bidirectional"))
      (node (ref "ATHRU_TEB") (pin "40") (pinfunction "40_40") (pintype "bidirectional"))
    )
    (net (code "216") (name "Net-(ATHRU_BEB-Pad41)") (class "Default")
      (node (ref "ATHRU_BEB") (pin "41") (pinfunction "41_41") (pintype "bidirectional"))
      (node (ref "ATHRU_TEB") (pin "41") (pinfunction "41_41") (pintype "bidirectional"))
    )
    (net (code "217") (name "Net-(ATHRU_BEB-Pad42)") (class "Default")
      (node (ref "ATHRU_BEB") (pin "42") (pinfunction "42_42") (pintype "bidirectional"))
      (node (ref "ATHRU_TEB") (pin "42") (pinfunction "42_42") (pintype "bidirectional"))
    )
    (net (code "218") (name "Net-(ATHRU_BEB-Pad43)") (class "Default")
      (node (ref "ATHRU_BEB") (pin "43") (pinfunction "43_43") (pintype "bidirectional"))
      (node (ref "ATHRU_TEB") (pin "43") (pinfunction "43_43") (pintype "bidirectional"))
    )
    (net (code "219") (name "Net-(ATHRU_BEB-Pad44)") (class "Default")
      (node (ref "ATHRU_BEB") (pin "44") (pinfunction "44_44") (pintype "bidirectional"))
      (node (ref "ATHRU_TEB") (pin "44") (pinfunction "44_44") (pintype "bidirectional"))
    )
    (net (code "220") (name "Net-(ATHRU_BEB-Pad45)") (class "Default")
      (node (ref "ATHRU_BEB") (pin "45") (pinfunction "45_45") (pintype "bidirectional"))
      (node (ref "ATHRU_TEB") (pin "45") (pinfunction "45_45") (pintype "bidirectional"))
    )
    (net (code "221") (name "Net-(ATHRU_BEB-Pad46)") (class "Default")
      (node (ref "ATHRU_BEB") (pin "46") (pinfunction "46_46") (pintype "bidirectional"))
      (node (ref "ATHRU_TEB") (pin "46") (pinfunction "46_46") (pintype "bidirectional"))
    )
    (net (code "222") (name "Net-(ATHRU_BEB-Pad47)") (class "Default")
      (node (ref "ATHRU_BEB") (pin "47") (pinfunction "47_47") (pintype "bidirectional"))
      (node (ref "ATHRU_TEB") (pin "47") (pinfunction "47_47") (pintype "bidirectional"))
    )
    (net (code "223") (name "Net-(ATHRU_BEB-Pad48)") (class "Default")
      (node (ref "ATHRU_BEB") (pin "48") (pinfunction "48_48") (pintype "bidirectional"))
      (node (ref "ATHRU_TEB") (pin "48") (pinfunction "48_48") (pintype "bidirectional"))
    )
    (net (code "224") (name "Net-(ATHRU_BEB-Pad49)") (class "Default")
      (node (ref "ATHRU_BEB") (pin "49") (pinfunction "49_49") (pintype "bidirectional"))
      (node (ref "ATHRU_TEB") (pin "49") (pinfunction "49_49") (pintype "bidirectional"))
    )
    (net (code "225") (name "Net-(ATHRU_BEB-Pad50)") (class "Default")
      (node (ref "ATHRU_BEB") (pin "50") (pinfunction "50_50") (pintype "bidirectional"))
      (node (ref "ATHRU_TEB") (pin "50") (pinfunction "50_50") (pintype "bidirectional"))
    )
    (net (code "226") (name "Net-(ATHRU_BEB-Pad51)") (class "Default")
      (node (ref "ATHRU_BEB") (pin "51") (pinfunction "51_51") (pintype "bidirectional"))
      (node (ref "ATHRU_TEB") (pin "51") (pinfunction "51_51") (pintype "bidirectional"))
    )
    (net (code "227") (name "Net-(ATHRU_BEB-Pad52)") (class "Default")
      (node (ref "ATHRU_BEB") (pin "52") (pinfunction "52_52") (pintype "bidirectional"))
      (node (ref "ATHRU_TEB") (pin "52") (pinfunction "52_52") (pintype "bidirectional"))
    )
    (net (code "228") (name "Net-(ATHRU_BEB-Pad53)") (class "Default")
      (node (ref "ATHRU_BEB") (pin "53") (pinfunction "53_53") (pintype "bidirectional"))
      (node (ref "ATHRU_TEB") (pin "53") (pinfunction "53_53") (pintype "bidirectional"))
    )
    (net (code "229") (name "Net-(ATHRU_BEB-Pad54)") (class "Default")
      (node (ref "ATHRU_BEB") (pin "54") (pinfunction "54_54") (pintype "bidirectional"))
      (node (ref "ATHRU_TEB") (pin "54") (pinfunction "54_54") (pintype "bidirectional"))
    )
    (net (code "230") (name "Net-(ATHRU_BEB-Pad55)") (class "Default")
      (node (ref "ATHRU_BEB") (pin "55") (pinfunction "55_55") (pintype "bidirectional"))
      (node (ref "ATHRU_TEB") (pin "55") (pinfunction "55_55") (pintype "bidirectional"))
    )
    (net (code "231") (name "Net-(ATHRU_BEB-Pad56)") (class "Default")
      (node (ref "ATHRU_BEB") (pin "56") (pinfunction "56_56") (pintype "bidirectional"))
      (node (ref "ATHRU_TEB") (pin "56") (pinfunction "56_56") (pintype "bidirectional"))
    )
    (net (code "232") (name "Net-(ATHRU_BEB-Pad57)") (class "Default")
      (node (ref "ATHRU_BEB") (pin "57") (pinfunction "57_57") (pintype "bidirectional"))
      (node (ref "ATHRU_TEB") (pin "57") (pinfunction "57_57") (pintype "bidirectional"))
    )
    (net (code "233") (name "Net-(ATHRU_BEB-Pad58)") (class "Default")
      (node (ref "ATHRU_BEB") (pin "58") (pinfunction "58_58") (pintype "bidirectional"))
      (node (ref "ATHRU_TEB") (pin "58") (pinfunction "58_58") (pintype "bidirectional"))
    )
    (net (code "234") (name "Net-(ATHRU_BEB-Pad59)") (class "Default")
      (node (ref "ATHRU_BEB") (pin "59") (pinfunction "59_59") (pintype "bidirectional"))
      (node (ref "ATHRU_TEB") (pin "59") (pinfunction "59_59") (pintype "bidirectional"))
    )
    (net (code "235") (name "Net-(ATHRU_BEB-Pad60)") (class "Default")
      (node (ref "ATHRU_BEB") (pin "60") (pinfunction "60_60") (pintype "bidirectional"))
      (node (ref "ATHRU_TEB") (pin "60") (pinfunction "60_60") (pintype "bidirectional"))
    )
    (net (code "236") (name "Net-(ATHRU_BEB-Pad61)") (class "Default")
      (node (ref "ATHRU_BEB") (pin "61") (pinfunction "61_61") (pintype "bidirectional"))
      (node (ref "ATHRU_TEB") (pin "61") (pinfunction "61_61") (pintype "bidirectional"))
    )
    (net (code "237") (name "Net-(ATHRU_BEB-Pad62)") (class "Default")
      (node (ref "ATHRU_BEB") (pin "62") (pinfunction "62_62") (pintype "bidirectional"))
      (node (ref "ATHRU_TEB") (pin "62") (pinfunction "62_62") (pintype "bidirectional"))
    )
    (net (code "238") (name "Net-(ATHRU_BEB-Pad63)") (class "Default")
      (node (ref "ATHRU_BEB") (pin "63") (pinfunction "63_63") (pintype "bidirectional"))
      (node (ref "ATHRU_TEB") (pin "63") (pinfunction "63_63") (pintype "bidirectional"))
    )
    (net (code "239") (name "Net-(ATHRU_BEB-Pad64)") (class "Default")
      (node (ref "ATHRU_BEB") (pin "64") (pinfunction "64_64") (pintype "bidirectional"))
      (node (ref "ATHRU_TEB") (pin "64") (pinfunction "64_64") (pintype "bidirectional"))
    )
    (net (code "240") (name "Net-(ATHRU_BEB-Pad65)") (class "Default")
      (node (ref "ATHRU_BEB") (pin "65") (pinfunction "65_65") (pintype "bidirectional"))
      (node (ref "ATHRU_TEB") (pin "65") (pinfunction "65_65") (pintype "bidirectional"))
    )
    (net (code "241") (name "Net-(ATHRU_BEB-Pad66)") (class "Default")
      (node (ref "ATHRU_BEB") (pin "66") (pinfunction "66_66") (pintype "bidirectional"))
      (node (ref "ATHRU_TEB") (pin "66") (pinfunction "66_66") (pintype "bidirectional"))
    )
    (net (code "242") (name "Net-(ATHRU_BEB-Pad67)") (class "Default")
      (node (ref "ATHRU_BEB") (pin "67") (pinfunction "67_67") (pintype "bidirectional"))
      (node (ref "ATHRU_TEB") (pin "67") (pinfunction "67_67") (pintype "bidirectional"))
    )
    (net (code "243") (name "Net-(ATHRU_BEB-Pad68)") (class "Default")
      (node (ref "ATHRU_BEB") (pin "68") (pinfunction "68_68") (pintype "bidirectional"))
      (node (ref "ATHRU_TEB") (pin "68") (pinfunction "68_68") (pintype "bidirectional"))
    )
    (net (code "244") (name "Net-(ATHRU_BWB-Pad2)") (class "Default")
      (node (ref "ATHRU_BWB") (pin "2") (pinfunction "2_2") (pintype "bidirectional"))
      (node (ref "ATHRU_TWB") (pin "2") (pinfunction "2_2") (pintype "bidirectional"))
    )
    (net (code "245") (name "Net-(ATHRU_BWB-Pad3)") (class "Default")
      (node (ref "ATHRU_BWB") (pin "3") (pinfunction "3_3") (pintype "bidirectional"))
      (node (ref "ATHRU_TWB") (pin "3") (pinfunction "3_3") (pintype "bidirectional"))
    )
    (net (code "246") (name "Net-(ATHRU_BWB-Pad4)") (class "Default")
      (node (ref "ATHRU_BWB") (pin "4") (pinfunction "4_4") (pintype "bidirectional"))
      (node (ref "ATHRU_TWB") (pin "4") (pinfunction "4_4") (pintype "bidirectional"))
    )
    (net (code "247") (name "Net-(ATHRU_BWB-Pad5)") (class "Default")
      (node (ref "ATHRU_BWB") (pin "5") (pinfunction "5_5") (pintype "bidirectional"))
      (node (ref "ATHRU_TWB") (pin "5") (pinfunction "5_5") (pintype "bidirectional"))
    )
    (net (code "248") (name "Net-(ATHRU_BWB-Pad6)") (class "Default")
      (node (ref "ATHRU_BWB") (pin "6") (pinfunction "6_6") (pintype "bidirectional"))
      (node (ref "ATHRU_TWB") (pin "6") (pinfunction "6_6") (pintype "bidirectional"))
    )
    (net (code "249") (name "Net-(ATHRU_BWB-Pad7)") (class "Default")
      (node (ref "ATHRU_BWB") (pin "7") (pinfunction "7_7") (pintype "bidirectional"))
      (node (ref "ATHRU_TWB") (pin "7") (pinfunction "7_7") (pintype "bidirectional"))
    )
    (net (code "250") (name "Net-(ATHRU_BWB-Pad8)") (class "Default")
      (node (ref "ATHRU_BWB") (pin "8") (pinfunction "8_8") (pintype "bidirectional"))
      (node (ref "ATHRU_TWB") (pin "8") (pinfunction "8_8") (pintype "bidirectional"))
    )
    (net (code "251") (name "Net-(ATHRU_BWB-Pad9)") (class "Default")
      (node (ref "ATHRU_BWB") (pin "9") (pinfunction "9_9") (pintype "bidirectional"))
      (node (ref "ATHRU_TWB") (pin "9") (pinfunction "9_9") (pintype "bidirectional"))
    )
    (net (code "252") (name "Net-(ATHRU_BWB-Pad10)") (class "Default")
      (node (ref "ATHRU_BWB") (pin "10") (pinfunction "10_10") (pintype "bidirectional"))
      (node (ref "ATHRU_TWB") (pin "10") (pinfunction "10_10") (pintype "bidirectional"))
    )
    (net (code "253") (name "Net-(ATHRU_BWB-Pad11)") (class "Default")
      (node (ref "ATHRU_BWB") (pin "11") (pinfunction "11_11") (pintype "bidirectional"))
      (node (ref "ATHRU_TWB") (pin "11") (pinfunction "11_11") (pintype "bidirectional"))
    )
    (net (code "254") (name "Net-(ATHRU_BWB-Pad12)") (class "Default")
      (node (ref "ATHRU_BWB") (pin "12") (pinfunction "12_12") (pintype "bidirectional"))
      (node (ref "ATHRU_TWB") (pin "12") (pinfunction "12_12") (pintype "bidirectional"))
    )
    (net (code "255") (name "Net-(ATHRU_BWB-Pad13)") (class "Default")
      (node (ref "ATHRU_BWB") (pin "13") (pinfunction "13_13") (pintype "bidirectional"))
      (node (ref "ATHRU_TWB") (pin "13") (pinfunction "13_13") (pintype "bidirectional"))
    )
    (net (code "256") (name "Net-(ATHRU_BWB-Pad14)") (class "Default")
      (node (ref "ATHRU_BWB") (pin "14") (pinfunction "14_14") (pintype "bidirectional"))
      (node (ref "ATHRU_TWB") (pin "14") (pinfunction "14_14") (pintype "bidirectional"))
    )
    (net (code "257") (name "Net-(ATHRU_BWB-Pad15)") (class "Default")
      (node (ref "ATHRU_BWB") (pin "15") (pinfunction "15_15") (pintype "bidirectional"))
      (node (ref "ATHRU_TWB") (pin "15") (pinfunction "15_15") (pintype "bidirectional"))
    )
    (net (code "258") (name "Net-(ATHRU_BWB-Pad16)") (class "Default")
      (node (ref "ATHRU_BWB") (pin "16") (pinfunction "16_16") (pintype "bidirectional"))
      (node (ref "ATHRU_TWB") (pin "16") (pinfunction "16_16") (pintype "bidirectional"))
    )
    (net (code "259") (name "Net-(ATHRU_BWB-Pad17)") (class "Default")
      (node (ref "ATHRU_BWB") (pin "17") (pinfunction "17_17") (pintype "bidirectional"))
      (node (ref "ATHRU_TWB") (pin "17") (pinfunction "17_17") (pintype "bidirectional"))
    )
    (net (code "260") (name "Net-(ATHRU_BWB-Pad18)") (class "Default")
      (node (ref "ATHRU_BWB") (pin "18") (pinfunction "18_18") (pintype "bidirectional"))
      (node (ref "ATHRU_TWB") (pin "18") (pinfunction "18_18") (pintype "bidirectional"))
    )
    (net (code "261") (name "Net-(ATHRU_BWB-Pad19)") (class "Default")
      (node (ref "ATHRU_BWB") (pin "19") (pinfunction "19_19") (pintype "bidirectional"))
      (node (ref "ATHRU_TWB") (pin "19") (pinfunction "19_19") (pintype "bidirectional"))
    )
    (net (code "262") (name "Net-(ATHRU_BWB-Pad20)") (class "Default")
      (node (ref "ATHRU_BWB") (pin "20") (pinfunction "20_20") (pintype "bidirectional"))
      (node (ref "ATHRU_TWB") (pin "20") (pinfunction "20_20") (pintype "bidirectional"))
    )
    (net (code "263") (name "Net-(ATHRU_BWB-Pad21)") (class "Default")
      (node (ref "ATHRU_BWB") (pin "21") (pinfunction "21_21") (pintype "bidirectional"))
      (node (ref "ATHRU_TWB") (pin "21") (pinfunction "21_21") (pintype "bidirectional"))
    )
    (net (code "264") (name "Net-(ATHRU_BWB-Pad22)") (class "Default")
      (node (ref "ATHRU_BWB") (pin "22") (pinfunction "22_22") (pintype "bidirectional"))
      (node (ref "ATHRU_TWB") (pin "22") (pinfunction "22_22") (pintype "bidirectional"))
    )
    (net (code "265") (name "Net-(ATHRU_BWB-Pad23)") (class "Default")
      (node (ref "ATHRU_BWB") (pin "23") (pinfunction "23_23") (pintype "bidirectional"))
      (node (ref "ATHRU_TWB") (pin "23") (pinfunction "23_23") (pintype "bidirectional"))
    )
    (net (code "266") (name "Net-(ATHRU_BWB-Pad24)") (class "Default")
      (node (ref "ATHRU_BWB") (pin "24") (pinfunction "24_24") (pintype "bidirectional"))
      (node (ref "ATHRU_TWB") (pin "24") (pinfunction "24_24") (pintype "bidirectional"))
    )
    (net (code "267") (name "Net-(ATHRU_BWB-Pad25)") (class "Default")
      (node (ref "ATHRU_BWB") (pin "25") (pinfunction "25_25") (pintype "bidirectional"))
      (node (ref "ATHRU_TWB") (pin "25") (pinfunction "25_25") (pintype "bidirectional"))
    )
    (net (code "268") (name "Net-(ATHRU_BWB-Pad26)") (class "Default")
      (node (ref "ATHRU_BWB") (pin "26") (pinfunction "26_26") (pintype "bidirectional"))
      (node (ref "ATHRU_TWB") (pin "26") (pinfunction "26_26") (pintype "bidirectional"))
    )
    (net (code "269") (name "Net-(ATHRU_BWB-Pad27)") (class "Default")
      (node (ref "ATHRU_BWB") (pin "27") (pinfunction "27_27") (pintype "bidirectional"))
      (node (ref "ATHRU_TWB") (pin "27") (pinfunction "27_27") (pintype "bidirectional"))
    )
    (net (code "270") (name "Net-(ATHRU_BWB-Pad28)") (class "Default")
      (node (ref "ATHRU_BWB") (pin "28") (pinfunction "28_28") (pintype "bidirectional"))
      (node (ref "ATHRU_TWB") (pin "28") (pinfunction "28_28") (pintype "bidirectional"))
    )
    (net (code "271") (name "Net-(ATHRU_BWB-Pad29)") (class "Default")
      (node (ref "ATHRU_BWB") (pin "29") (pinfunction "29_29") (pintype "bidirectional"))
      (node (ref "ATHRU_TWB") (pin "29") (pinfunction "29_29") (pintype "bidirectional"))
    )
    (net (code "272") (name "Net-(ATHRU_BWB-Pad30)") (class "Default")
      (node (ref "ATHRU_BWB") (pin "30") (pinfunction "30_30") (pintype "bidirectional"))
      (node (ref "ATHRU_TWB") (pin "30") (pinfunction "30_30") (pintype "bidirectional"))
    )
    (net (code "273") (name "Net-(ATHRU_BWB-Pad31)") (class "Default")
      (node (ref "ATHRU_BWB") (pin "31") (pinfunction "31_31") (pintype "bidirectional"))
      (node (ref "ATHRU_TWB") (pin "31") (pinfunction "31_31") (pintype "bidirectional"))
    )
    (net (code "274") (name "Net-(ATHRU_BWB-Pad32)") (class "Default")
      (node (ref "ATHRU_BWB") (pin "32") (pinfunction "32_32") (pintype "bidirectional"))
      (node (ref "ATHRU_TWB") (pin "32") (pinfunction "32_32") (pintype "bidirectional"))
    )
    (net (code "275") (name "Net-(ATHRU_BWB-Pad33)") (class "Default")
      (node (ref "ATHRU_BWB") (pin "33") (pinfunction "33_33") (pintype "bidirectional"))
      (node (ref "ATHRU_TWB") (pin "33") (pinfunction "33_33") (pintype "bidirectional"))
    )
    (net (code "276") (name "Net-(ATHRU_BWB-Pad37)") (class "Default")
      (node (ref "ATHRU_BWB") (pin "37") (pinfunction "37_37") (pintype "bidirectional"))
      (node (ref "ATHRU_TWB") (pin "37") (pinfunction "37_37") (pintype "bidirectional"))
    )
    (net (code "277") (name "Net-(ATHRU_BWB-Pad38)") (class "Default")
      (node (ref "ATHRU_BWB") (pin "38") (pinfunction "38_38") (pintype "bidirectional"))
      (node (ref "ATHRU_TWB") (pin "38") (pinfunction "38_38") (pintype "bidirectional"))
    )
    (net (code "278") (name "Net-(ATHRU_BWB-Pad39)") (class "Default")
      (node (ref "ATHRU_BWB") (pin "39") (pinfunction "39_39") (pintype "bidirectional"))
      (node (ref "ATHRU_TWB") (pin "39") (pinfunction "39_39") (pintype "bidirectional"))
    )
    (net (code "279") (name "Net-(ATHRU_BWB-Pad40)") (class "Default")
      (node (ref "ATHRU_BWB") (pin "40") (pinfunction "40_40") (pintype "bidirectional"))
      (node (ref "ATHRU_TWB") (pin "40") (pinfunction "40_40") (pintype "bidirectional"))
    )
    (net (code "280") (name "Net-(ATHRU_BWB-Pad41)") (class "Default")
      (node (ref "ATHRU_BWB") (pin "41") (pinfunction "41_41") (pintype "bidirectional"))
      (node (ref "ATHRU_TWB") (pin "41") (pinfunction "41_41") (pintype "bidirectional"))
    )
    (net (code "281") (name "Net-(ATHRU_BWB-Pad42)") (class "Default")
      (node (ref "ATHRU_BWB") (pin "42") (pinfunction "42_42") (pintype "bidirectional"))
      (node (ref "ATHRU_TWB") (pin "42") (pinfunction "42_42") (pintype "bidirectional"))
    )
    (net (code "282") (name "Net-(ATHRU_BWB-Pad43)") (class "Default")
      (node (ref "ATHRU_BWB") (pin "43") (pinfunction "43_43") (pintype "bidirectional"))
      (node (ref "ATHRU_TWB") (pin "43") (pinfunction "43_43") (pintype "bidirectional"))
    )
    (net (code "283") (name "Net-(ATHRU_BWB-Pad44)") (class "Default")
      (node (ref "ATHRU_BWB") (pin "44") (pinfunction "44_44") (pintype "bidirectional"))
      (node (ref "ATHRU_TWB") (pin "44") (pinfunction "44_44") (pintype "bidirectional"))
    )
    (net (code "284") (name "Net-(ATHRU_BWB-Pad45)") (class "Default")
      (node (ref "ATHRU_BWB") (pin "45") (pinfunction "45_45") (pintype "bidirectional"))
      (node (ref "ATHRU_TWB") (pin "45") (pinfunction "45_45") (pintype "bidirectional"))
    )
    (net (code "285") (name "Net-(ATHRU_BWB-Pad46)") (class "Default")
      (node (ref "ATHRU_BWB") (pin "46") (pinfunction "46_46") (pintype "bidirectional"))
      (node (ref "ATHRU_TWB") (pin "46") (pinfunction "46_46") (pintype "bidirectional"))
    )
    (net (code "286") (name "Net-(ATHRU_BWB-Pad47)") (class "Default")
      (node (ref "ATHRU_BWB") (pin "47") (pinfunction "47_47") (pintype "bidirectional"))
      (node (ref "ATHRU_TWB") (pin "47") (pinfunction "47_47") (pintype "bidirectional"))
    )
    (net (code "287") (name "Net-(ATHRU_BWB-Pad48)") (class "Default")
      (node (ref "ATHRU_BWB") (pin "48") (pinfunction "48_48") (pintype "bidirectional"))
      (node (ref "ATHRU_TWB") (pin "48") (pinfunction "48_48") (pintype "bidirectional"))
    )
    (net (code "288") (name "Net-(ATHRU_BWB-Pad49)") (class "Default")
      (node (ref "ATHRU_BWB") (pin "49") (pinfunction "49_49") (pintype "bidirectional"))
      (node (ref "ATHRU_TWB") (pin "49") (pinfunction "49_49") (pintype "bidirectional"))
    )
    (net (code "289") (name "Net-(ATHRU_BWB-Pad50)") (class "Default")
      (node (ref "ATHRU_BWB") (pin "50") (pinfunction "50_50") (pintype "bidirectional"))
      (node (ref "ATHRU_TWB") (pin "50") (pinfunction "50_50") (pintype "bidirectional"))
    )
    (net (code "290") (name "Net-(ATHRU_BWB-Pad51)") (class "Default")
      (node (ref "ATHRU_BWB") (pin "51") (pinfunction "51_51") (pintype "bidirectional"))
      (node (ref "ATHRU_TWB") (pin "51") (pinfunction "51_51") (pintype "bidirectional"))
    )
    (net (code "291") (name "Net-(ATHRU_BWB-Pad52)") (class "Default")
      (node (ref "ATHRU_BWB") (pin "52") (pinfunction "52_52") (pintype "bidirectional"))
      (node (ref "ATHRU_TWB") (pin "52") (pinfunction "52_52") (pintype "bidirectional"))
    )
    (net (code "292") (name "Net-(ATHRU_BWB-Pad53)") (class "Default")
      (node (ref "ATHRU_BWB") (pin "53") (pinfunction "53_53") (pintype "bidirectional"))
      (node (ref "ATHRU_TWB") (pin "53") (pinfunction "53_53") (pintype "bidirectional"))
    )
    (net (code "293") (name "Net-(ATHRU_BWB-Pad54)") (class "Default")
      (node (ref "ATHRU_BWB") (pin "54") (pinfunction "54_54") (pintype "bidirectional"))
      (node (ref "ATHRU_TWB") (pin "54") (pinfunction "54_54") (pintype "bidirectional"))
    )
    (net (code "294") (name "Net-(ATHRU_BWB-Pad55)") (class "Default")
      (node (ref "ATHRU_BWB") (pin "55") (pinfunction "55_55") (pintype "bidirectional"))
      (node (ref "ATHRU_TWB") (pin "55") (pinfunction "55_55") (pintype "bidirectional"))
    )
    (net (code "295") (name "Net-(ATHRU_BWB-Pad56)") (class "Default")
      (node (ref "ATHRU_BWB") (pin "56") (pinfunction "56_56") (pintype "bidirectional"))
      (node (ref "ATHRU_TWB") (pin "56") (pinfunction "56_56") (pintype "bidirectional"))
    )
    (net (code "296") (name "Net-(ATHRU_BWB-Pad57)") (class "Default")
      (node (ref "ATHRU_BWB") (pin "57") (pinfunction "57_57") (pintype "bidirectional"))
      (node (ref "ATHRU_TWB") (pin "57") (pinfunction "57_57") (pintype "bidirectional"))
    )
    (net (code "297") (name "Net-(ATHRU_BWB-Pad58)") (class "Default")
      (node (ref "ATHRU_BWB") (pin "58") (pinfunction "58_58") (pintype "bidirectional"))
      (node (ref "ATHRU_TWB") (pin "58") (pinfunction "58_58") (pintype "bidirectional"))
    )
    (net (code "298") (name "Net-(ATHRU_BWB-Pad59)") (class "Default")
      (node (ref "ATHRU_BWB") (pin "59") (pinfunction "59_59") (pintype "bidirectional"))
      (node (ref "ATHRU_TWB") (pin "59") (pinfunction "59_59") (pintype "bidirectional"))
    )
    (net (code "299") (name "Net-(ATHRU_BWB-Pad60)") (class "Default")
      (node (ref "ATHRU_BWB") (pin "60") (pinfunction "60_60") (pintype "bidirectional"))
      (node (ref "ATHRU_TWB") (pin "60") (pinfunction "60_60") (pintype "bidirectional"))
    )
    (net (code "300") (name "Net-(ATHRU_BWB-Pad61)") (class "Default")
      (node (ref "ATHRU_BWB") (pin "61") (pinfunction "61_61") (pintype "bidirectional"))
      (node (ref "ATHRU_TWB") (pin "61") (pinfunction "61_61") (pintype "bidirectional"))
    )
    (net (code "301") (name "Net-(ATHRU_BWB-Pad62)") (class "Default")
      (node (ref "ATHRU_BWB") (pin "62") (pinfunction "62_62") (pintype "bidirectional"))
      (node (ref "ATHRU_TWB") (pin "62") (pinfunction "62_62") (pintype "bidirectional"))
    )
    (net (code "302") (name "Net-(ATHRU_BWB-Pad63)") (class "Default")
      (node (ref "ATHRU_BWB") (pin "63") (pinfunction "63_63") (pintype "bidirectional"))
      (node (ref "ATHRU_TWB") (pin "63") (pinfunction "63_63") (pintype "bidirectional"))
    )
    (net (code "303") (name "Net-(ATHRU_BWB-Pad64)") (class "Default")
      (node (ref "ATHRU_BWB") (pin "64") (pinfunction "64_64") (pintype "bidirectional"))
      (node (ref "ATHRU_TWB") (pin "64") (pinfunction "64_64") (pintype "bidirectional"))
    )
    (net (code "304") (name "Net-(ATHRU_BWB-Pad65)") (class "Default")
      (node (ref "ATHRU_BWB") (pin "65") (pinfunction "65_65") (pintype "bidirectional"))
      (node (ref "ATHRU_TWB") (pin "65") (pinfunction "65_65") (pintype "bidirectional"))
    )
    (net (code "305") (name "Net-(ATHRU_BWB-Pad66)") (class "Default")
      (node (ref "ATHRU_BWB") (pin "66") (pinfunction "66_66") (pintype "bidirectional"))
      (node (ref "ATHRU_TWB") (pin "66") (pinfunction "66_66") (pintype "bidirectional"))
    )
    (net (code "306") (name "Net-(ATHRU_BWB-Pad67)") (class "Default")
      (node (ref "ATHRU_BWB") (pin "67") (pinfunction "67_67") (pintype "bidirectional"))
      (node (ref "ATHRU_TWB") (pin "67") (pinfunction "67_67") (pintype "bidirectional"))
    )
    (net (code "307") (name "Net-(ATHRU_BWB-Pad68)") (class "Default")
      (node (ref "ATHRU_BWB") (pin "68") (pinfunction "68_68") (pintype "bidirectional"))
      (node (ref "ATHRU_TWB") (pin "68") (pinfunction "68_68") (pintype "bidirectional"))
    )
    (net (code "308") (name "Net-(C4-Pad2)") (class "Default")
      (node (ref "C4") (pin "2") (pinfunction "2_2") (pintype "passive"))
      (node (ref "R8") (pin "2") (pinfunction "2_2") (pintype "passive"))
      (node (ref "U1") (pin "XOUT") (pinfunction "XOUT_XOUT") (pintype "bidirectional"))
    )
    (net (code "309") (name "Net-(C5-Pad2)") (class "Default")
      (node (ref "C5") (pin "2") (pinfunction "2_2") (pintype "passive"))
      (node (ref "R9") (pin "2") (pinfunction "2_2") (pintype "passive"))
      (node (ref "U1") (pin "YOUT") (pinfunction "YOUT_YOUT") (pintype "bidirectional"))
    )
    (net (code "310") (name "Net-(C6-Pad2)") (class "Default")
      (node (ref "C6") (pin "2") (pinfunction "2_2") (pintype "passive"))
      (node (ref "R10") (pin "2") (pinfunction "2_2") (pintype "passive"))
      (node (ref "U1") (pin "ZOUT") (pinfunction "ZOUT_ZOUT") (pintype "bidirectional"))
    )
    (net (code "311") (name "Net-(U2-1Y1)") (class "Default")
      (node (ref "PLATE") (pin "B2") (pinfunction "B2_B2") (pintype "bidirectional"))
      (node (ref "U2") (pin "1") (pinfunction "2Y1_1") (pintype "bidirectional"))
      (node (ref "U2") (pin "13") (pinfunction "1Y1_13") (pintype "bidirectional"))
    )
    (net (code "312") (name "Net-(U2-3Y0)") (class "Default")
      (node (ref "R4") (pin "2") (pinfunction "2_2") (pintype "passive"))
      (node (ref "U2") (pin "5") (pinfunction "3Y0_5") (pintype "bidirectional"))
    )
    (net (code "313") (name "Net-(U2-S1)") (class "Default")
      (node (ref "PLATE") (pin "T1") (pinfunction "T1_T1") (pintype "bidirectional"))
      (node (ref "R7") (pin "2") (pinfunction "2_2") (pintype "passive"))
      (node (ref "U2") (pin "11") (pinfunction "S1_11") (pintype "input"))
    )
    (net (code "314") (name "Net-(U2-S2)") (class "Default")
      (node (ref "PLATE") (pin "T2") (pinfunction "T2_T2") (pintype "bidirectional"))
      (node (ref "R6") (pin "2") (pinfunction "2_2") (pintype "passive"))
      (node (ref "U2") (pin "10") (pinfunction "S2_10") (pintype "input"))
    )
    (net (code "315") (name "Net-(U2-S3)") (class "Default")
      (node (ref "PLATE") (pin "T3") (pinfunction "T3_T3") (pintype "bidirectional"))
      (node (ref "R5") (pin "2") (pinfunction "2_2") (pintype "passive"))
      (node (ref "U2") (pin "9") (pinfunction "S3_9") (pintype "input"))
    )
    (net (code "316") (name "VCC") (class "Default")
      (node (ref "AMP_A") (pin "B17") (pinfunction "VDD2_B17") (pintype "power_in"))
      (node (ref "AMP_A") (pin "B18") (pinfunction "VDD3_B18") (pintype "power_in"))
      (node (ref "AMP_A") (pin "B2") (pinfunction "VESD_B2") (pintype "power_in"))
      (node (ref "AMP_A") (pin "B21") (pinfunction "LVDS_EN_B21") (pintype "input"))
      (node (ref "AMP_A") (pin "B4") (pinfunction "VDD1_B4") (pintype "power_in"))
      (node (ref "AMP_B") (pin "B17") (pinfunction "VDD2_B17") (pintype "power_in"))
      (node (ref "AMP_B") (pin "B18") (pinfunction "VDD3_B18") (pintype "power_in"))
      (node (ref "AMP_B") (pin "B2") (pinfunction "VESD_B2") (pintype "power_in"))
      (node (ref "AMP_B") (pin "B21") (pinfunction "LVDS_EN_B21") (pintype "input"))
      (node (ref "AMP_B") (pin "B4") (pinfunction "VDD1_B4") (pintype "power_in"))
      (node (ref "C2") (pin "1") (pinfunction "1_1") (pintype "passive"))
      (node (ref "C3") (pin "1") (pinfunction "1_1") (pintype "passive"))
      (node (ref "C8") (pin "1") (pinfunction "1_1") (pintype "passive"))
      (node (ref "DIO_TEA") (pin "10") (pinfunction "10_10") (pintype "bidirectional"))
      (node (ref "U1") (pin "VS1") (pinfunction "VS1_VS1") (pintype "bidirectional"))
      (node (ref "U1") (pin "VS2") (pinfunction "VS2_VS2") (pintype "bidirectional"))
      (node (ref "U2") (pin "16") (pinfunction "VCC_16") (pintype "power_in"))
      (node (ref "VCC1") (pin "1") (pinfunction "1_1") (pintype "passive"))
      (node (ref "VCC2") (pin "1") (pinfunction "1_1") (pintype "passive"))
    )
    (net (code "317") (name "unconnected-(AMP_A-AUXOUT-PadB20)") (class "Default")
      (node (ref "AMP_A") (pin "B20") (pinfunction "AUXOUT_B20") (pintype "tri_state"))
    )
    (net (code "318") (name "unconnected-(AMP_A-REF_ELEC1-PadA)") (class "Default")
      (node (ref "AMP_A") (pin "A") (pinfunction "REF_ELEC1_A") (pintype "input"))
    )
    (net (code "319") (name "unconnected-(AMP_A-REF_ELEC2-PadB)") (class "Default")
      (node (ref "AMP_A") (pin "B") (pinfunction "REF_ELEC2_B") (pintype "input"))
    )
    (net (code "320") (name "unconnected-(AMP_B-REF_ELEC1-PadA)") (class "Default")
      (node (ref "AMP_B") (pin "A") (pinfunction "REF_ELEC1_A") (pintype "input"))
    )
    (net (code "321") (name "unconnected-(AMP_B-REF_ELEC2-PadB)") (class "Default")
      (node (ref "AMP_B") (pin "B") (pinfunction "REF_ELEC2_B") (pintype "input"))
    )
    (net (code "322") (name "unconnected-(MECH_TNB-Pad1)") (class "Default")
      (node (ref "MECH_TNB") (pin "1") (pinfunction "1_1") (pintype "bidirectional"))
    )
    (net (code "323") (name "unconnected-(MECH_TNB-Pad2)") (class "Default")
      (node (ref "MECH_TNB") (pin "2") (pinfunction "2_2") (pintype "bidirectional"))
    )
    (net (code "324") (name "unconnected-(MECH_TNB-Pad3)") (class "Default")
      (node (ref "MECH_TNB") (pin "3") (pinfunction "3_3") (pintype "bidirectional"))
    )
    (net (code "325") (name "unconnected-(MECH_TNB-Pad4)") (class "Default")
      (node (ref "MECH_TNB") (pin "4") (pinfunction "4_4") (pintype "bidirectional"))
    )
    (net (code "326") (name "unconnected-(MECH_TNB-Pad5)") (class "Default")
      (node (ref "MECH_TNB") (pin "5") (pinfunction "5_5") (pintype "bidirectional"))
    )
    (net (code "327") (name "unconnected-(MECH_TNB-Pad6)") (class "Default")
      (node (ref "MECH_TNB") (pin "6") (pinfunction "6_6") (pintype "bidirectional"))
    )
    (net (code "328") (name "unconnected-(MECH_TNB-Pad7)") (class "Default")
      (node (ref "MECH_TNB") (pin "7") (pinfunction "7_7") (pintype "bidirectional"))
    )
    (net (code "329") (name "unconnected-(MECH_TNB-Pad8)") (class "Default")
      (node (ref "MECH_TNB") (pin "8") (pinfunction "8_8") (pintype "bidirectional"))
    )
    (net (code "330") (name "unconnected-(MECH_TNB-Pad9)") (class "Default")
      (node (ref "MECH_TNB") (pin "9") (pinfunction "9_9") (pintype "bidirectional"))
    )
    (net (code "331") (name "unconnected-(MECH_TNB-Pad10)") (class "Default")
      (node (ref "MECH_TNB") (pin "10") (pinfunction "10_10") (pintype "bidirectional"))
    )
    (net (code "332") (name "unconnected-(MECH_TNB-Pad11)") (class "Default")
      (node (ref "MECH_TNB") (pin "11") (pinfunction "11_11") (pintype "bidirectional"))
    )
    (net (code "333") (name "unconnected-(MECH_TNB-Pad12)") (class "Default")
      (node (ref "MECH_TNB") (pin "12") (pinfunction "12_12") (pintype "bidirectional"))
    )
    (net (code "334") (name "unconnected-(MECH_TNB-Pad13)") (class "Default")
      (node (ref "MECH_TNB") (pin "13") (pinfunction "13_13") (pintype "bidirectional"))
    )
    (net (code "335") (name "unconnected-(MECH_TNB-Pad14)") (class "Default")
      (node (ref "MECH_TNB") (pin "14") (pinfunction "14_14") (pintype "bidirectional"))
    )
    (net (code "336") (name "unconnected-(MECH_TNB-Pad15)") (class "Default")
      (node (ref "MECH_TNB") (pin "15") (pinfunction "15_15") (pintype "bidirectional"))
    )
    (net (code "337") (name "unconnected-(MECH_TNB-Pad16)") (class "Default")
      (node (ref "MECH_TNB") (pin "16") (pinfunction "16_16") (pintype "bidirectional"))
    )
    (net (code "338") (name "unconnected-(MECH_TNB-Pad17)") (class "Default")
      (node (ref "MECH_TNB") (pin "17") (pinfunction "17_17") (pintype "bidirectional"))
    )
    (net (code "339") (name "unconnected-(MECH_TNB-Pad18)") (class "Default")
      (node (ref "MECH_TNB") (pin "18") (pinfunction "18_18") (pintype "bidirectional"))
    )
    (net (code "340") (name "unconnected-(MECH_TNB-Pad19)") (class "Default")
      (node (ref "MECH_TNB") (pin "19") (pinfunction "19_19") (pintype "bidirectional"))
    )
    (net (code "341") (name "unconnected-(MECH_TNB-Pad20)") (class "Default")
      (node (ref "MECH_TNB") (pin "20") (pinfunction "20_20") (pintype "bidirectional"))
    )
    (net (code "342") (name "unconnected-(MECH_TNB-Pad21)") (class "Default")
      (node (ref "MECH_TNB") (pin "21") (pinfunction "21_21") (pintype "bidirectional"))
    )
    (net (code "343") (name "unconnected-(MECH_TNB-Pad22)") (class "Default")
      (node (ref "MECH_TNB") (pin "22") (pinfunction "22_22") (pintype "bidirectional"))
    )
    (net (code "344") (name "unconnected-(MECH_TNB-Pad23)") (class "Default")
      (node (ref "MECH_TNB") (pin "23") (pinfunction "23_23") (pintype "bidirectional"))
    )
    (net (code "345") (name "unconnected-(MECH_TNB-Pad24)") (class "Default")
      (node (ref "MECH_TNB") (pin "24") (pinfunction "24_24") (pintype "bidirectional"))
    )
    (net (code "346") (name "unconnected-(MECH_TNB-Pad25)") (class "Default")
      (node (ref "MECH_TNB") (pin "25") (pinfunction "25_25") (pintype "bidirectional"))
    )
    (net (code "347") (name "unconnected-(MECH_TNB-Pad26)") (class "Default")
      (node (ref "MECH_TNB") (pin "26") (pinfunction "26_26") (pintype "bidirectional"))
    )
    (net (code "348") (name "unconnected-(MECH_TNB-Pad27)") (class "Default")
      (node (ref "MECH_TNB") (pin "27") (pinfunction "27_27") (pintype "bidirectional"))
    )
    (net (code "349") (name "unconnected-(MECH_TNB-Pad28)") (class "Default")
      (node (ref "MECH_TNB") (pin "28") (pinfunction "28_28") (pintype "bidirectional"))
    )
    (net (code "350") (name "unconnected-(MECH_TNB-Pad29)") (class "Default")
      (node (ref "MECH_TNB") (pin "29") (pinfunction "29_29") (pintype "bidirectional"))
    )
    (net (code "351") (name "unconnected-(MECH_TNB-Pad30)") (class "Default")
      (node (ref "MECH_TNB") (pin "30") (pinfunction "30_30") (pintype "bidirectional"))
    )
    (net (code "352") (name "unconnected-(MECH_TNB-Pad31)") (class "Default")
      (node (ref "MECH_TNB") (pin "31") (pinfunction "31_31") (pintype "bidirectional"))
    )
    (net (code "353") (name "unconnected-(MECH_TNB-Pad32)") (class "Default")
      (node (ref "MECH_TNB") (pin "32") (pinfunction "32_32") (pintype "bidirectional"))
    )
    (net (code "354") (name "unconnected-(MECH_TNB-Pad33)") (class "Default")
      (node (ref "MECH_TNB") (pin "33") (pinfunction "33_33") (pintype "bidirectional"))
    )
    (net (code "355") (name "unconnected-(MECH_TNB-Pad34)") (class "Default")
      (node (ref "MECH_TNB") (pin "34") (pinfunction "34_34") (pintype "bidirectional"))
    )
    (net (code "356") (name "unconnected-(MECH_TNB-Pad35)") (class "Default")
      (node (ref "MECH_TNB") (pin "35") (pinfunction "35_35") (pintype "bidirectional"))
    )
    (net (code "357") (name "unconnected-(MECH_TNB-Pad36)") (class "Default")
      (node (ref "MECH_TNB") (pin "36") (pinfunction "36_36") (pintype "bidirectional"))
    )
    (net (code "358") (name "unconnected-(MECH_TNB-Pad37)") (class "Default")
      (node (ref "MECH_TNB") (pin "37") (pinfunction "37_37") (pintype "bidirectional"))
    )
    (net (code "359") (name "unconnected-(MECH_TNB-Pad38)") (class "Default")
      (node (ref "MECH_TNB") (pin "38") (pinfunction "38_38") (pintype "bidirectional"))
    )
    (net (code "360") (name "unconnected-(MECH_TNB-Pad39)") (class "Default")
      (node (ref "MECH_TNB") (pin "39") (pinfunction "39_39") (pintype "bidirectional"))
    )
    (net (code "361") (name "unconnected-(MECH_TNB-Pad40)") (class "Default")
      (node (ref "MECH_TNB") (pin "40") (pinfunction "40_40") (pintype "bidirectional"))
    )
    (net (code "362") (name "unconnected-(MECH_TNB-Pad41)") (class "Default")
      (node (ref "MECH_TNB") (pin "41") (pinfunction "41_41") (pintype "bidirectional"))
    )
    (net (code "363") (name "unconnected-(MECH_TNB-Pad42)") (class "Default")
      (node (ref "MECH_TNB") (pin "42") (pinfunction "42_42") (pintype "bidirectional"))
    )
    (net (code "364") (name "unconnected-(MECH_TNB-Pad43)") (class "Default")
      (node (ref "MECH_TNB") (pin "43") (pinfunction "43_43") (pintype "bidirectional"))
    )
    (net (code "365") (name "unconnected-(MECH_TNB-Pad44)") (class "Default")
      (node (ref "MECH_TNB") (pin "44") (pinfunction "44_44") (pintype "bidirectional"))
    )
    (net (code "366") (name "unconnected-(MECH_TNB-Pad45)") (class "Default")
      (node (ref "MECH_TNB") (pin "45") (pinfunction "45_45") (pintype "bidirectional"))
    )
    (net (code "367") (name "unconnected-(MECH_TNB-Pad46)") (class "Default")
      (node (ref "MECH_TNB") (pin "46") (pinfunction "46_46") (pintype "bidirectional"))
    )
    (net (code "368") (name "unconnected-(MECH_TNB-Pad47)") (class "Default")
      (node (ref "MECH_TNB") (pin "47") (pinfunction "47_47") (pintype "bidirectional"))
    )
    (net (code "369") (name "unconnected-(MECH_TNB-Pad48)") (class "Default")
      (node (ref "MECH_TNB") (pin "48") (pinfunction "48_48") (pintype "bidirectional"))
    )
    (net (code "370") (name "unconnected-(MECH_TNB-Pad49)") (class "Default")
      (node (ref "MECH_TNB") (pin "49") (pinfunction "49_49") (pintype "bidirectional"))
    )
    (net (code "371") (name "unconnected-(MECH_TNB-Pad50)") (class "Default")
      (node (ref "MECH_TNB") (pin "50") (pinfunction "50_50") (pintype "bidirectional"))
    )
    (net (code "372") (name "unconnected-(MECH_TNB-Pad51)") (class "Default")
      (node (ref "MECH_TNB") (pin "51") (pinfunction "51_51") (pintype "bidirectional"))
    )
    (net (code "373") (name "unconnected-(MECH_TNB-Pad52)") (class "Default")
      (node (ref "MECH_TNB") (pin "52") (pinfunction "52_52") (pintype "bidirectional"))
    )
    (net (code "374") (name "unconnected-(MECH_TNB-Pad53)") (class "Default")
      (node (ref "MECH_TNB") (pin "53") (pinfunction "53_53") (pintype "bidirectional"))
    )
    (net (code "375") (name "unconnected-(MECH_TNB-Pad54)") (class "Default")
      (node (ref "MECH_TNB") (pin "54") (pinfunction "54_54") (pintype "bidirectional"))
    )
    (net (code "376") (name "unconnected-(MECH_TNB-Pad55)") (class "Default")
      (node (ref "MECH_TNB") (pin "55") (pinfunction "55_55") (pintype "bidirectional"))
    )
    (net (code "377") (name "unconnected-(MECH_TNB-Pad56)") (class "Default")
      (node (ref "MECH_TNB") (pin "56") (pinfunction "56_56") (pintype "bidirectional"))
    )
    (net (code "378") (name "unconnected-(MECH_TNB-Pad57)") (class "Default")
      (node (ref "MECH_TNB") (pin "57") (pinfunction "57_57") (pintype "bidirectional"))
    )
    (net (code "379") (name "unconnected-(MECH_TNB-Pad58)") (class "Default")
      (node (ref "MECH_TNB") (pin "58") (pinfunction "58_58") (pintype "bidirectional"))
    )
    (net (code "380") (name "unconnected-(MECH_TNB-Pad59)") (class "Default")
      (node (ref "MECH_TNB") (pin "59") (pinfunction "59_59") (pintype "bidirectional"))
    )
    (net (code "381") (name "unconnected-(MECH_TNB-Pad60)") (class "Default")
      (node (ref "MECH_TNB") (pin "60") (pinfunction "60_60") (pintype "bidirectional"))
    )
    (net (code "382") (name "unconnected-(MECH_TNB-Pad61)") (class "Default")
      (node (ref "MECH_TNB") (pin "61") (pinfunction "61_61") (pintype "bidirectional"))
    )
    (net (code "383") (name "unconnected-(MECH_TNB-Pad62)") (class "Default")
      (node (ref "MECH_TNB") (pin "62") (pinfunction "62_62") (pintype "bidirectional"))
    )
    (net (code "384") (name "unconnected-(MECH_TNB-Pad63)") (class "Default")
      (node (ref "MECH_TNB") (pin "63") (pinfunction "63_63") (pintype "bidirectional"))
    )
    (net (code "385") (name "unconnected-(MECH_TNB-Pad64)") (class "Default")
      (node (ref "MECH_TNB") (pin "64") (pinfunction "64_64") (pintype "bidirectional"))
    )
    (net (code "386") (name "unconnected-(MECH_TNB-Pad65)") (class "Default")
      (node (ref "MECH_TNB") (pin "65") (pinfunction "65_65") (pintype "bidirectional"))
    )
    (net (code "387") (name "unconnected-(MECH_TNB-Pad66)") (class "Default")
      (node (ref "MECH_TNB") (pin "66") (pinfunction "66_66") (pintype "bidirectional"))
    )
    (net (code "388") (name "unconnected-(MECH_TNB-Pad67)") (class "Default")
      (node (ref "MECH_TNB") (pin "67") (pinfunction "67_67") (pintype "bidirectional"))
    )
    (net (code "389") (name "unconnected-(MECH_TNB-Pad68)") (class "Default")
      (node (ref "MECH_TNB") (pin "68") (pinfunction "68_68") (pintype "bidirectional"))
    )
    (net (code "390") (name "unconnected-(MECH_TNB-Pad69)") (class "Default")
      (node (ref "MECH_TNB") (pin "69") (pinfunction "69_69") (pintype "bidirectional"))
    )
    (net (code "391") (name "unconnected-(MECH_TNB-Pad70)") (class "Default")
      (node (ref "MECH_TNB") (pin "70") (pinfunction "70_70") (pintype "bidirectional"))
    )
    (net (code "392") (name "unconnected-(MECH_TSB-Pad1)") (class "Default")
      (node (ref "MECH_TSB") (pin "1") (pinfunction "1_1") (pintype "bidirectional"))
    )
    (net (code "393") (name "unconnected-(MECH_TSB-Pad2)") (class "Default")
      (node (ref "MECH_TSB") (pin "2") (pinfunction "2_2") (pintype "bidirectional"))
    )
    (net (code "394") (name "unconnected-(MECH_TSB-Pad3)") (class "Default")
      (node (ref "MECH_TSB") (pin "3") (pinfunction "3_3") (pintype "bidirectional"))
    )
    (net (code "395") (name "unconnected-(MECH_TSB-Pad4)") (class "Default")
      (node (ref "MECH_TSB") (pin "4") (pinfunction "4_4") (pintype "bidirectional"))
    )
    (net (code "396") (name "unconnected-(MECH_TSB-Pad5)") (class "Default")
      (node (ref "MECH_TSB") (pin "5") (pinfunction "5_5") (pintype "bidirectional"))
    )
    (net (code "397") (name "unconnected-(MECH_TSB-Pad6)") (class "Default")
      (node (ref "MECH_TSB") (pin "6") (pinfunction "6_6") (pintype "bidirectional"))
    )
    (net (code "398") (name "unconnected-(MECH_TSB-Pad7)") (class "Default")
      (node (ref "MECH_TSB") (pin "7") (pinfunction "7_7") (pintype "bidirectional"))
    )
    (net (code "399") (name "unconnected-(MECH_TSB-Pad8)") (class "Default")
      (node (ref "MECH_TSB") (pin "8") (pinfunction "8_8") (pintype "bidirectional"))
    )
    (net (code "400") (name "unconnected-(MECH_TSB-Pad9)") (class "Default")
      (node (ref "MECH_TSB") (pin "9") (pinfunction "9_9") (pintype "bidirectional"))
    )
    (net (code "401") (name "unconnected-(MECH_TSB-Pad10)") (class "Default")
      (node (ref "MECH_TSB") (pin "10") (pinfunction "10_10") (pintype "bidirectional"))
    )
    (net (code "402") (name "unconnected-(MECH_TSB-Pad11)") (class "Default")
      (node (ref "MECH_TSB") (pin "11") (pinfunction "11_11") (pintype "bidirectional"))
    )
    (net (code "403") (name "unconnected-(MECH_TSB-Pad12)") (class "Default")
      (node (ref "MECH_TSB") (pin "12") (pinfunction "12_12") (pintype "bidirectional"))
    )
    (net (code "404") (name "unconnected-(MECH_TSB-Pad13)") (class "Default")
      (node (ref "MECH_TSB") (pin "13") (pinfunction "13_13") (pintype "bidirectional"))
    )
    (net (code "405") (name "unconnected-(MECH_TSB-Pad14)") (class "Default")
      (node (ref "MECH_TSB") (pin "14") (pinfunction "14_14") (pintype "bidirectional"))
    )
    (net (code "406") (name "unconnected-(MECH_TSB-Pad15)") (class "Default")
      (node (ref "MECH_TSB") (pin "15") (pinfunction "15_15") (pintype "bidirectional"))
    )
    (net (code "407") (name "unconnected-(MECH_TSB-Pad16)") (class "Default")
      (node (ref "MECH_TSB") (pin "16") (pinfunction "16_16") (pintype "bidirectional"))
    )
    (net (code "408") (name "unconnected-(MECH_TSB-Pad17)") (class "Default")
      (node (ref "MECH_TSB") (pin "17") (pinfunction "17_17") (pintype "bidirectional"))
    )
    (net (code "409") (name "unconnected-(MECH_TSB-Pad18)") (class "Default")
      (node (ref "MECH_TSB") (pin "18") (pinfunction "18_18") (pintype "bidirectional"))
    )
    (net (code "410") (name "unconnected-(MECH_TSB-Pad19)") (class "Default")
      (node (ref "MECH_TSB") (pin "19") (pinfunction "19_19") (pintype "bidirectional"))
    )
    (net (code "411") (name "unconnected-(MECH_TSB-Pad20)") (class "Default")
      (node (ref "MECH_TSB") (pin "20") (pinfunction "20_20") (pintype "bidirectional"))
    )
    (net (code "412") (name "unconnected-(MECH_TSB-Pad21)") (class "Default")
      (node (ref "MECH_TSB") (pin "21") (pinfunction "21_21") (pintype "bidirectional"))
    )
    (net (code "413") (name "unconnected-(MECH_TSB-Pad22)") (class "Default")
      (node (ref "MECH_TSB") (pin "22") (pinfunction "22_22") (pintype "bidirectional"))
    )
    (net (code "414") (name "unconnected-(MECH_TSB-Pad23)") (class "Default")
      (node (ref "MECH_TSB") (pin "23") (pinfunction "23_23") (pintype "bidirectional"))
    )
    (net (code "415") (name "unconnected-(MECH_TSB-Pad24)") (class "Default")
      (node (ref "MECH_TSB") (pin "24") (pinfunction "24_24") (pintype "bidirectional"))
    )
    (net (code "416") (name "unconnected-(MECH_TSB-Pad25)") (class "Default")
      (node (ref "MECH_TSB") (pin "25") (pinfunction "25_25") (pintype "bidirectional"))
    )
    (net (code "417") (name "unconnected-(MECH_TSB-Pad26)") (class "Default")
      (node (ref "MECH_TSB") (pin "26") (pinfunction "26_26") (pintype "bidirectional"))
    )
    (net (code "418") (name "unconnected-(MECH_TSB-Pad27)") (class "Default")
      (node (ref "MECH_TSB") (pin "27") (pinfunction "27_27") (pintype "bidirectional"))
    )
    (net (code "419") (name "unconnected-(MECH_TSB-Pad28)") (class "Default")
      (node (ref "MECH_TSB") (pin "28") (pinfunction "28_28") (pintype "bidirectional"))
    )
    (net (code "420") (name "unconnected-(MECH_TSB-Pad29)") (class "Default")
      (node (ref "MECH_TSB") (pin "29") (pinfunction "29_29") (pintype "bidirectional"))
    )
    (net (code "421") (name "unconnected-(MECH_TSB-Pad30)") (class "Default")
      (node (ref "MECH_TSB") (pin "30") (pinfunction "30_30") (pintype "bidirectional"))
    )
    (net (code "422") (name "unconnected-(MECH_TSB-Pad31)") (class "Default")
      (node (ref "MECH_TSB") (pin "31") (pinfunction "31_31") (pintype "bidirectional"))
    )
    (net (code "423") (name "unconnected-(MECH_TSB-Pad32)") (class "Default")
      (node (ref "MECH_TSB") (pin "32") (pinfunction "32_32") (pintype "bidirectional"))
    )
    (net (code "424") (name "unconnected-(MECH_TSB-Pad33)") (class "Default")
      (node (ref "MECH_TSB") (pin "33") (pinfunction "33_33") (pintype "bidirectional"))
    )
    (net (code "425") (name "unconnected-(MECH_TSB-Pad34)") (class "Default")
      (node (ref "MECH_TSB") (pin "34") (pinfunction "34_34") (pintype "bidirectional"))
    )
    (net (code "426") (name "unconnected-(MECH_TSB-Pad35)") (class "Default")
      (node (ref "MECH_TSB") (pin "35") (pinfunction "35_35") (pintype "bidirectional"))
    )
    (net (code "427") (name "unconnected-(MECH_TSB-Pad36)") (class "Default")
      (node (ref "MECH_TSB") (pin "36") (pinfunction "36_36") (pintype "bidirectional"))
    )
    (net (code "428") (name "unconnected-(MECH_TSB-Pad37)") (class "Default")
      (node (ref "MECH_TSB") (pin "37") (pinfunction "37_37") (pintype "bidirectional"))
    )
    (net (code "429") (name "unconnected-(MECH_TSB-Pad38)") (class "Default")
      (node (ref "MECH_TSB") (pin "38") (pinfunction "38_38") (pintype "bidirectional"))
    )
    (net (code "430") (name "unconnected-(MECH_TSB-Pad39)") (class "Default")
      (node (ref "MECH_TSB") (pin "39") (pinfunction "39_39") (pintype "bidirectional"))
    )
    (net (code "431") (name "unconnected-(MECH_TSB-Pad40)") (class "Default")
      (node (ref "MECH_TSB") (pin "40") (pinfunction "40_40") (pintype "bidirectional"))
    )
    (net (code "432") (name "unconnected-(MECH_TSB-Pad41)") (class "Default")
      (node (ref "MECH_TSB") (pin "41") (pinfunction "41_41") (pintype "bidirectional"))
    )
    (net (code "433") (name "unconnected-(MECH_TSB-Pad42)") (class "Default")
      (node (ref "MECH_TSB") (pin "42") (pinfunction "42_42") (pintype "bidirectional"))
    )
    (net (code "434") (name "unconnected-(MECH_TSB-Pad43)") (class "Default")
      (node (ref "MECH_TSB") (pin "43") (pinfunction "43_43") (pintype "bidirectional"))
    )
    (net (code "435") (name "unconnected-(MECH_TSB-Pad44)") (class "Default")
      (node (ref "MECH_TSB") (pin "44") (pinfunction "44_44") (pintype "bidirectional"))
    )
    (net (code "436") (name "unconnected-(MECH_TSB-Pad45)") (class "Default")
      (node (ref "MECH_TSB") (pin "45") (pinfunction "45_45") (pintype "bidirectional"))
    )
    (net (code "437") (name "unconnected-(MECH_TSB-Pad46)") (class "Default")
      (node (ref "MECH_TSB") (pin "46") (pinfunction "46_46") (pintype "bidirectional"))
    )
    (net (code "438") (name "unconnected-(MECH_TSB-Pad47)") (class "Default")
      (node (ref "MECH_TSB") (pin "47") (pinfunction "47_47") (pintype "bidirectional"))
    )
    (net (code "439") (name "unconnected-(MECH_TSB-Pad48)") (class "Default")
      (node (ref "MECH_TSB") (pin "48") (pinfunction "48_48") (pintype "bidirectional"))
    )
    (net (code "440") (name "unconnected-(MECH_TSB-Pad49)") (class "Default")
      (node (ref "MECH_TSB") (pin "49") (pinfunction "49_49") (pintype "bidirectional"))
    )
    (net (code "441") (name "unconnected-(MECH_TSB-Pad50)") (class "Default")
      (node (ref "MECH_TSB") (pin "50") (pinfunction "50_50") (pintype "bidirectional"))
    )
    (net (code "442") (name "unconnected-(MECH_TSB-Pad51)") (class "Default")
      (node (ref "MECH_TSB") (pin "51") (pinfunction "51_51") (pintype "bidirectional"))
    )
    (net (code "443") (name "unconnected-(MECH_TSB-Pad52)") (class "Default")
      (node (ref "MECH_TSB") (pin "52") (pinfunction "52_52") (pintype "bidirectional"))
    )
    (net (code "444") (name "unconnected-(MECH_TSB-Pad53)") (class "Default")
      (node (ref "MECH_TSB") (pin "53") (pinfunction "53_53") (pintype "bidirectional"))
    )
    (net (code "445") (name "unconnected-(MECH_TSB-Pad54)") (class "Default")
      (node (ref "MECH_TSB") (pin "54") (pinfunction "54_54") (pintype "bidirectional"))
    )
    (net (code "446") (name "unconnected-(MECH_TSB-Pad55)") (class "Default")
      (node (ref "MECH_TSB") (pin "55") (pinfunction "55_55") (pintype "bidirectional"))
    )
    (net (code "447") (name "unconnected-(MECH_TSB-Pad56)") (class "Default")
      (node (ref "MECH_TSB") (pin "56") (pinfunction "56_56") (pintype "bidirectional"))
    )
    (net (code "448") (name "unconnected-(MECH_TSB-Pad57)") (class "Default")
      (node (ref "MECH_TSB") (pin "57") (pinfunction "57_57") (pintype "bidirectional"))
    )
    (net (code "449") (name "unconnected-(MECH_TSB-Pad58)") (class "Default")
      (node (ref "MECH_TSB") (pin "58") (pinfunction "58_58") (pintype "bidirectional"))
    )
    (net (code "450") (name "unconnected-(MECH_TSB-Pad59)") (class "Default")
      (node (ref "MECH_TSB") (pin "59") (pinfunction "59_59") (pintype "bidirectional"))
    )
    (net (code "451") (name "unconnected-(MECH_TSB-Pad60)") (class "Default")
      (node (ref "MECH_TSB") (pin "60") (pinfunction "60_60") (pintype "bidirectional"))
    )
    (net (code "452") (name "unconnected-(MECH_TSB-Pad61)") (class "Default")
      (node (ref "MECH_TSB") (pin "61") (pinfunction "61_61") (pintype "bidirectional"))
    )
    (net (code "453") (name "unconnected-(MECH_TSB-Pad62)") (class "Default")
      (node (ref "MECH_TSB") (pin "62") (pinfunction "62_62") (pintype "bidirectional"))
    )
    (net (code "454") (name "unconnected-(MECH_TSB-Pad63)") (class "Default")
      (node (ref "MECH_TSB") (pin "63") (pinfunction "63_63") (pintype "bidirectional"))
    )
    (net (code "455") (name "unconnected-(MECH_TSB-Pad64)") (class "Default")
      (node (ref "MECH_TSB") (pin "64") (pinfunction "64_64") (pintype "bidirectional"))
    )
    (net (code "456") (name "unconnected-(MECH_TSB-Pad65)") (class "Default")
      (node (ref "MECH_TSB") (pin "65") (pinfunction "65_65") (pintype "bidirectional"))
    )
    (net (code "457") (name "unconnected-(MECH_TSB-Pad66)") (class "Default")
      (node (ref "MECH_TSB") (pin "66") (pinfunction "66_66") (pintype "bidirectional"))
    )
    (net (code "458") (name "unconnected-(MECH_TSB-Pad67)") (class "Default")
      (node (ref "MECH_TSB") (pin "67") (pinfunction "67_67") (pintype "bidirectional"))
    )
    (net (code "459") (name "unconnected-(MECH_TSB-Pad68)") (class "Default")
      (node (ref "MECH_TSB") (pin "68") (pinfunction "68_68") (pintype "bidirectional"))
    )
    (net (code "460") (name "unconnected-(MECH_TSB-Pad69)") (class "Default")
      (node (ref "MECH_TSB") (pin "69") (pinfunction "69_69") (pintype "bidirectional"))
    )
    (net (code "461") (name "unconnected-(MECH_TSB-Pad70)") (class "Default")
      (node (ref "MECH_TSB") (pin "70") (pinfunction "70_70") (pintype "bidirectional"))
    )
    (net (code "462") (name "unconnected-(U1-PadNC3)") (class "Default")
      (node (ref "U1") (pin "NC3") (pinfunction "NC3_NC3") (pintype "bidirectional"))
    )
    (net (code "463") (name "unconnected-(U1-PadNC4)") (class "Default")
      (node (ref "U1") (pin "NC4") (pinfunction "NC4_NC4") (pintype "bidirectional"))
    )
    (net (code "464") (name "unconnected-(U1-PadNC5)") (class "Default")
      (node (ref "U1") (pin "NC5") (pinfunction "NC5_NC5") (pintype "bidirectional"))
    )
    (net (code "465") (name "unconnected-(U2-1Y0-Pad12)") (class "Default")
      (node (ref "U2") (pin "12") (pinfunction "1Y0_12") (pintype "bidirectional"))
    )
    (net (code "466") (name "unconnected-(U2-2Y0-Pad2)") (class "Default")
      (node (ref "U2") (pin "2") (pinfunction "2Y0_2") (pintype "bidirectional"))
    )
  )
)
